# Schematic1.net
KiCad netlist of a schematic drawn in Altium Designer
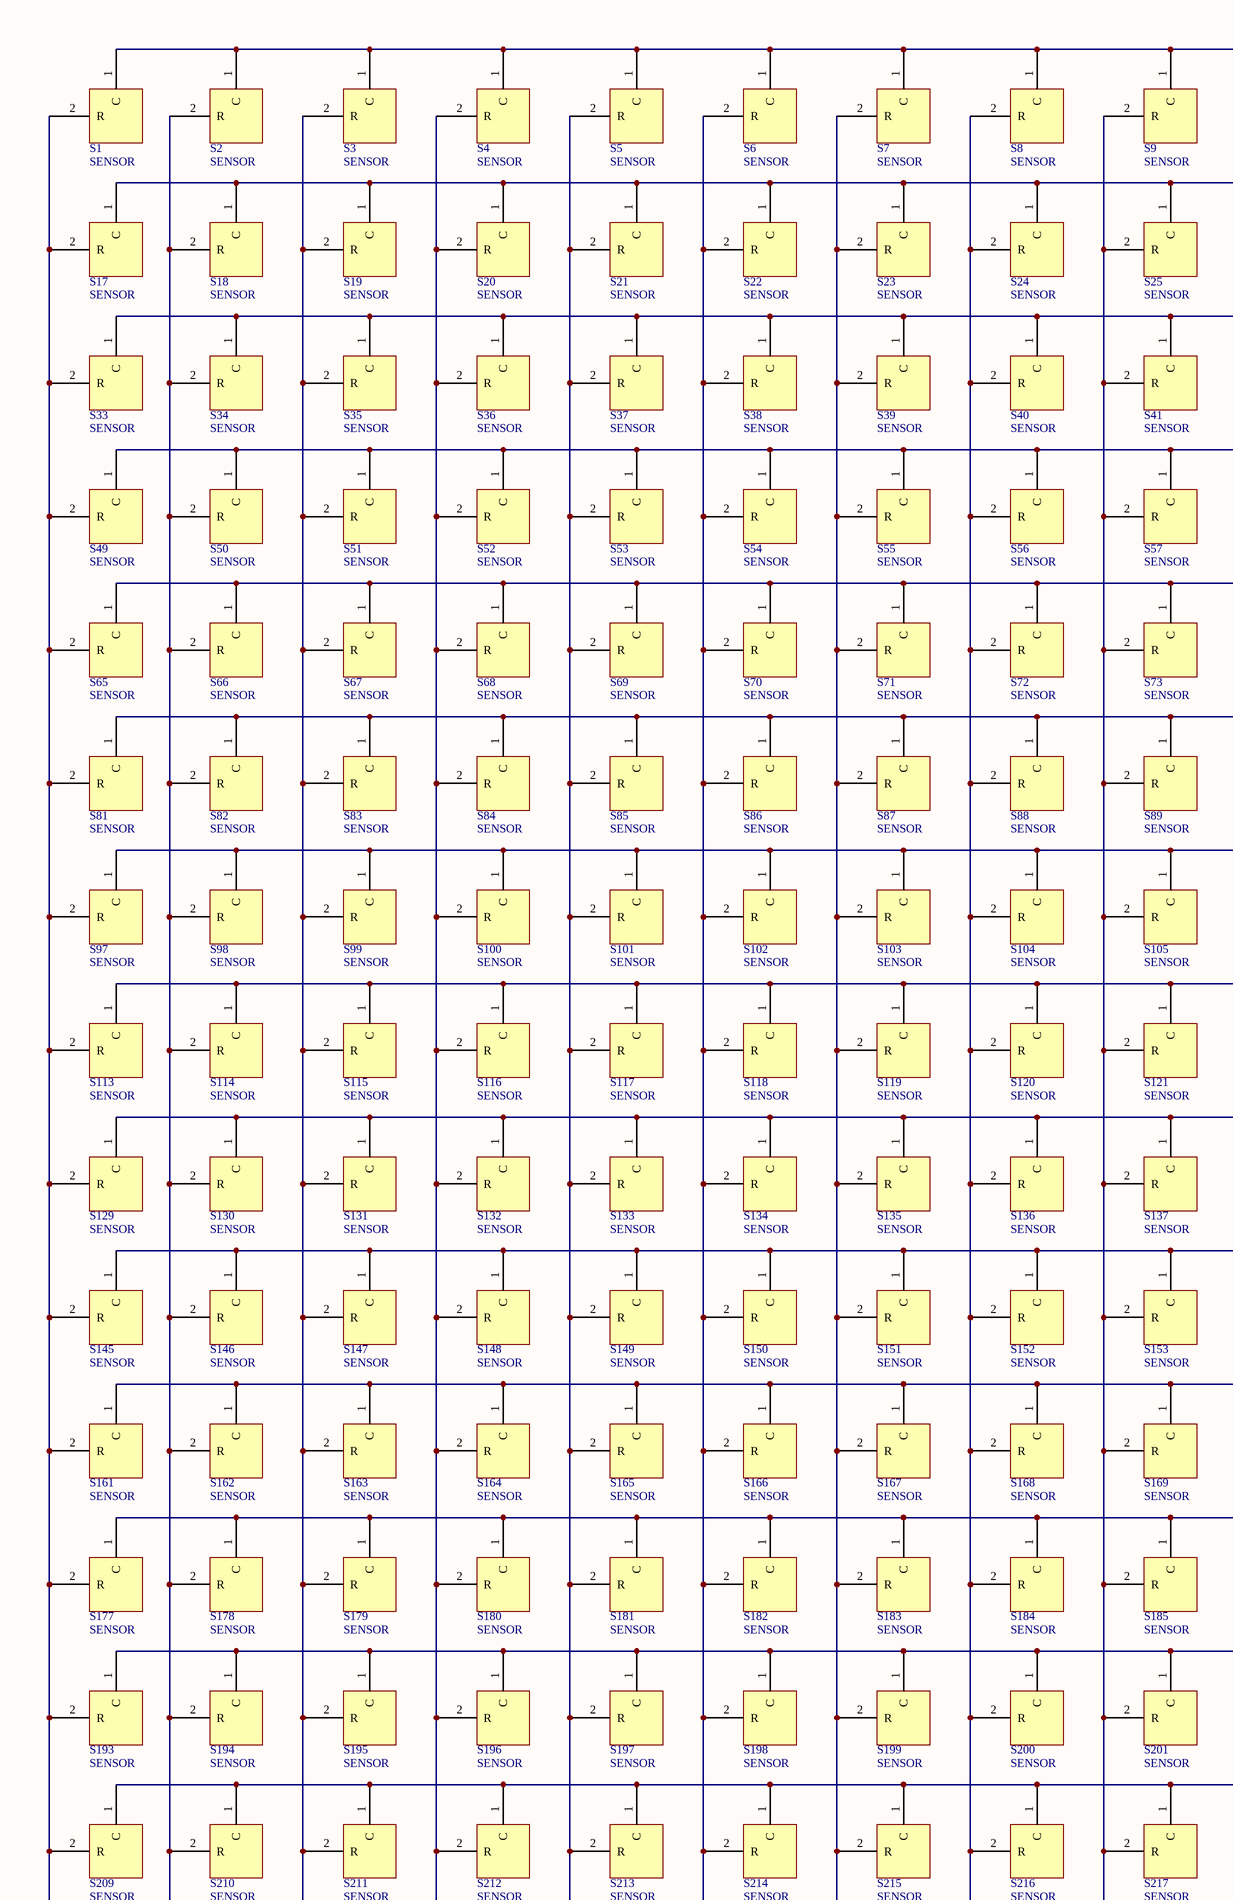
[diagram p0: Schematic1.SchDoc, top left]
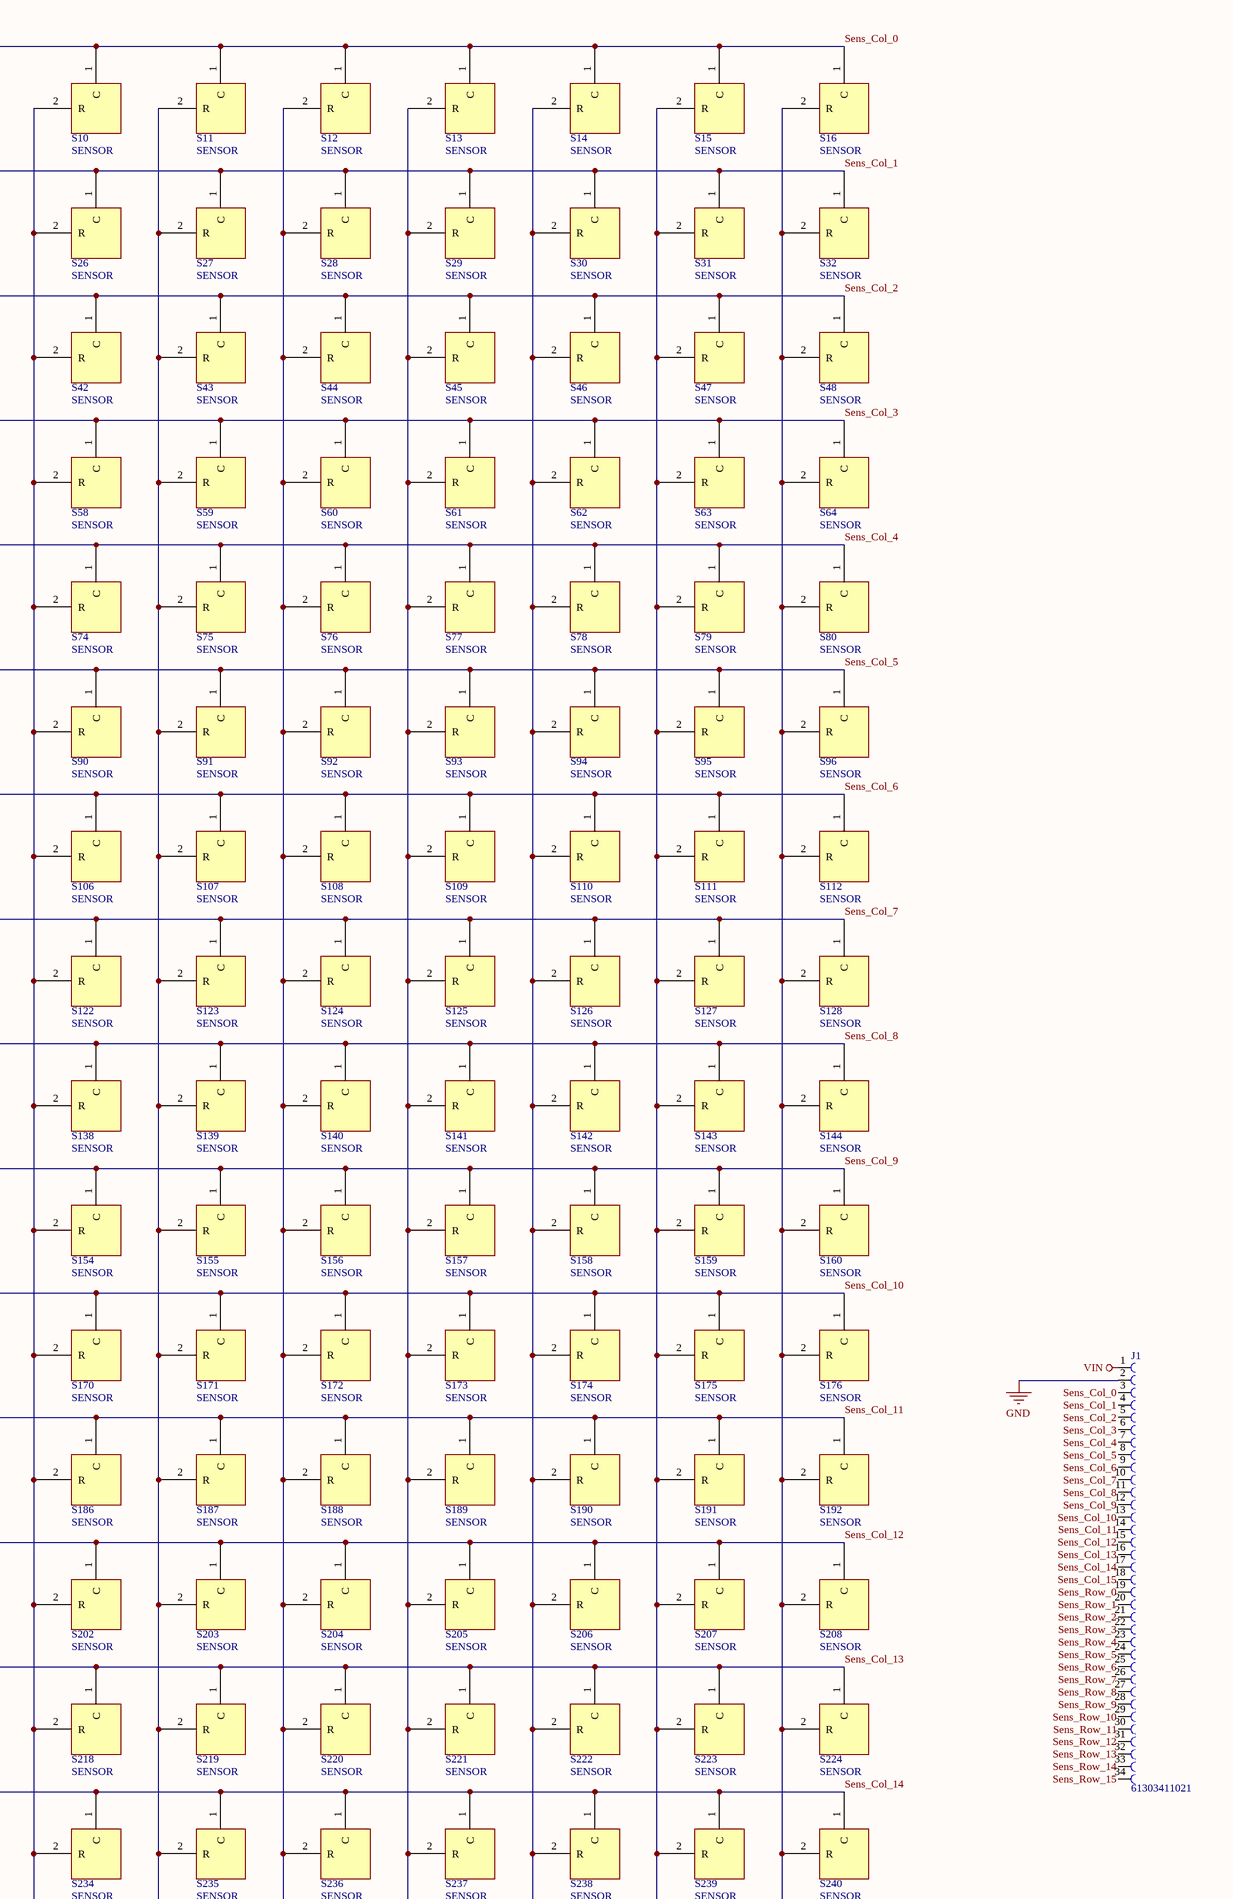
[diagram p1: Schematic1.SchDoc, top right]
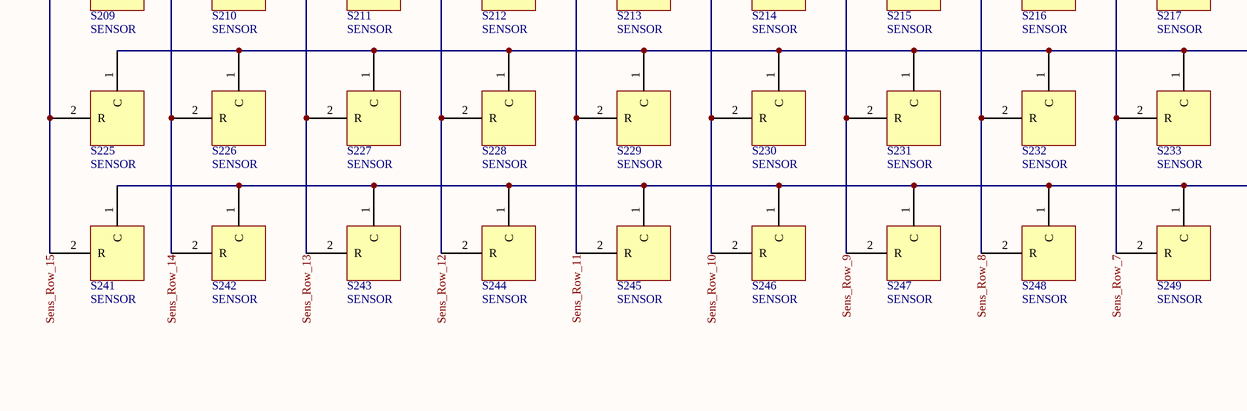
[diagram p2: Schematic1.SchDoc, bottom left]
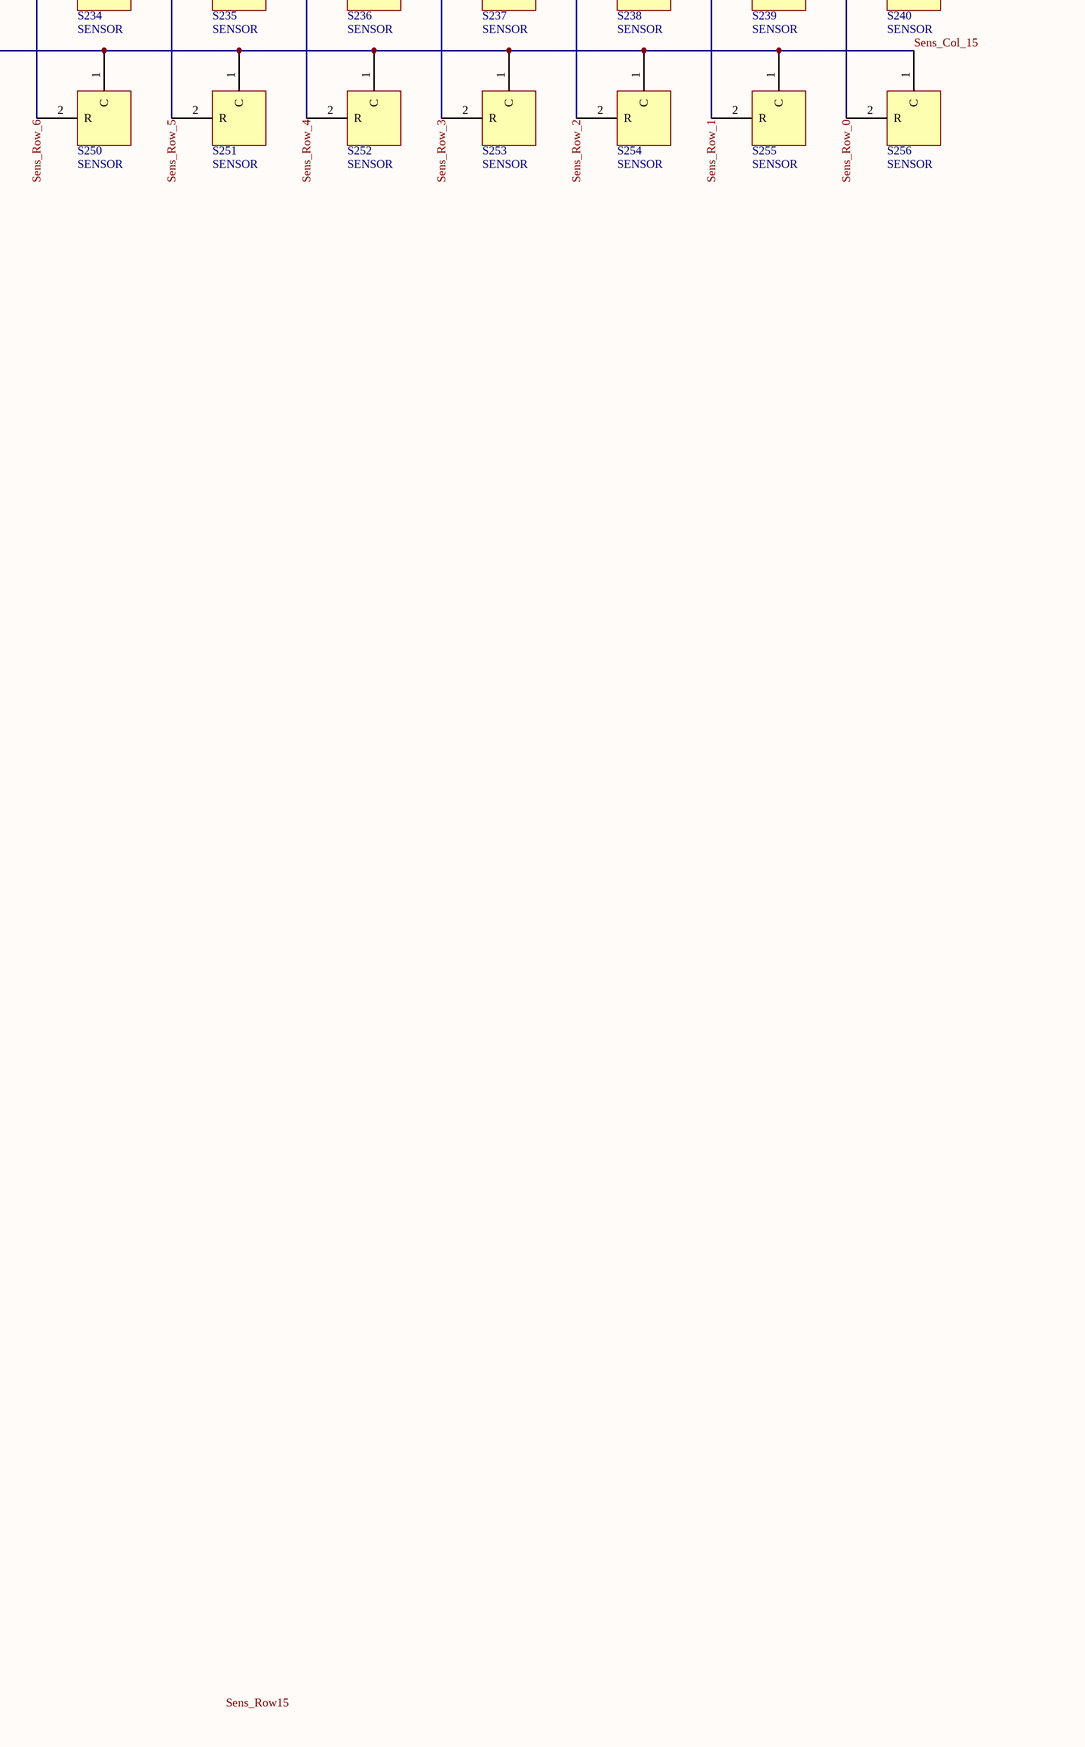
[diagram p3: Schematic1.SchDoc, bottom right]

(export (version "E")
  (design (tool "Eeschema 10.0.6"))
  (components
    (comp (ref "J1")
      (value "61303411021")
      (footprint "61303411021")
      (fields (field (name "MF") "{'manufacturer': u'~{W}xfcrth Elektronik'}"))
      (libsource (lib "SnapEDA_Library") (part "61303411021"))
    )
    (comp (ref "S1") (value "SENSOR") (footprint "SENSOR") (libsource (lib "SENSOR") (part "SENSOR")))
    (comp (ref "S2") (value "SENSOR") (footprint "SENSOR") (libsource (lib "SENSOR") (part "SENSOR")))
    (comp (ref "S3") (value "SENSOR") (footprint "SENSOR") (libsource (lib "SENSOR") (part "SENSOR")))
    (comp (ref "S4") (value "SENSOR") (footprint "SENSOR") (libsource (lib "SENSOR") (part "SENSOR")))
    (comp (ref "S5") (value "SENSOR") (footprint "SENSOR") (libsource (lib "SENSOR") (part "SENSOR")))
    (comp (ref "S6") (value "SENSOR") (footprint "SENSOR") (libsource (lib "SENSOR") (part "SENSOR")))
    (comp (ref "S7") (value "SENSOR") (footprint "SENSOR") (libsource (lib "SENSOR") (part "SENSOR")))
    (comp (ref "S8") (value "SENSOR") (footprint "SENSOR") (libsource (lib "SENSOR") (part "SENSOR")))
    (comp (ref "S9") (value "SENSOR") (footprint "SENSOR") (libsource (lib "SENSOR") (part "SENSOR")))
    (comp (ref "S10") (value "SENSOR") (footprint "SENSOR") (libsource (lib "SENSOR") (part "SENSOR")))
    (comp (ref "S11") (value "SENSOR") (footprint "SENSOR") (libsource (lib "SENSOR") (part "SENSOR")))
    (comp (ref "S12") (value "SENSOR") (footprint "SENSOR") (libsource (lib "SENSOR") (part "SENSOR")))
    (comp (ref "S13") (value "SENSOR") (footprint "SENSOR") (libsource (lib "SENSOR") (part "SENSOR")))
    (comp (ref "S14") (value "SENSOR") (footprint "SENSOR") (libsource (lib "SENSOR") (part "SENSOR")))
    (comp (ref "S15") (value "SENSOR") (footprint "SENSOR") (libsource (lib "SENSOR") (part "SENSOR")))
    (comp (ref "S16") (value "SENSOR") (footprint "SENSOR") (libsource (lib "SENSOR") (part "SENSOR")))
    (comp (ref "S17") (value "SENSOR") (footprint "SENSOR") (libsource (lib "SENSOR") (part "SENSOR")))
    (comp (ref "S18") (value "SENSOR") (footprint "SENSOR") (libsource (lib "SENSOR") (part "SENSOR")))
    (comp (ref "S19") (value "SENSOR") (footprint "SENSOR") (libsource (lib "SENSOR") (part "SENSOR")))
    (comp (ref "S20") (value "SENSOR") (footprint "SENSOR") (libsource (lib "SENSOR") (part "SENSOR")))
    (comp (ref "S21") (value "SENSOR") (footprint "SENSOR") (libsource (lib "SENSOR") (part "SENSOR")))
    (comp (ref "S22") (value "SENSOR") (footprint "SENSOR") (libsource (lib "SENSOR") (part "SENSOR")))
    (comp (ref "S23") (value "SENSOR") (footprint "SENSOR") (libsource (lib "SENSOR") (part "SENSOR")))
    (comp (ref "S24") (value "SENSOR") (footprint "SENSOR") (libsource (lib "SENSOR") (part "SENSOR")))
    (comp (ref "S25") (value "SENSOR") (footprint "SENSOR") (libsource (lib "SENSOR") (part "SENSOR")))
    (comp (ref "S26") (value "SENSOR") (footprint "SENSOR") (libsource (lib "SENSOR") (part "SENSOR")))
    (comp (ref "S27") (value "SENSOR") (footprint "SENSOR") (libsource (lib "SENSOR") (part "SENSOR")))
    (comp (ref "S28") (value "SENSOR") (footprint "SENSOR") (libsource (lib "SENSOR") (part "SENSOR")))
    (comp (ref "S29") (value "SENSOR") (footprint "SENSOR") (libsource (lib "SENSOR") (part "SENSOR")))
    (comp (ref "S30") (value "SENSOR") (footprint "SENSOR") (libsource (lib "SENSOR") (part "SENSOR")))
    (comp (ref "S31") (value "SENSOR") (footprint "SENSOR") (libsource (lib "SENSOR") (part "SENSOR")))
    (comp (ref "S32") (value "SENSOR") (footprint "SENSOR") (libsource (lib "SENSOR") (part "SENSOR")))
    (comp (ref "S33") (value "SENSOR") (footprint "SENSOR") (libsource (lib "SENSOR") (part "SENSOR")))
    (comp (ref "S34") (value "SENSOR") (footprint "SENSOR") (libsource (lib "SENSOR") (part "SENSOR")))
    (comp (ref "S35") (value "SENSOR") (footprint "SENSOR") (libsource (lib "SENSOR") (part "SENSOR")))
    (comp (ref "S36") (value "SENSOR") (footprint "SENSOR") (libsource (lib "SENSOR") (part "SENSOR")))
    (comp (ref "S37") (value "SENSOR") (footprint "SENSOR") (libsource (lib "SENSOR") (part "SENSOR")))
    (comp (ref "S38") (value "SENSOR") (footprint "SENSOR") (libsource (lib "SENSOR") (part "SENSOR")))
    (comp (ref "S39") (value "SENSOR") (footprint "SENSOR") (libsource (lib "SENSOR") (part "SENSOR")))
    (comp (ref "S40") (value "SENSOR") (footprint "SENSOR") (libsource (lib "SENSOR") (part "SENSOR")))
    (comp (ref "S41") (value "SENSOR") (footprint "SENSOR") (libsource (lib "SENSOR") (part "SENSOR")))
    (comp (ref "S42") (value "SENSOR") (footprint "SENSOR") (libsource (lib "SENSOR") (part "SENSOR")))
    (comp (ref "S43") (value "SENSOR") (footprint "SENSOR") (libsource (lib "SENSOR") (part "SENSOR")))
    (comp (ref "S44") (value "SENSOR") (footprint "SENSOR") (libsource (lib "SENSOR") (part "SENSOR")))
    (comp (ref "S45") (value "SENSOR") (footprint "SENSOR") (libsource (lib "SENSOR") (part "SENSOR")))
    (comp (ref "S46") (value "SENSOR") (footprint "SENSOR") (libsource (lib "SENSOR") (part "SENSOR")))
    (comp (ref "S47") (value "SENSOR") (footprint "SENSOR") (libsource (lib "SENSOR") (part "SENSOR")))
    (comp (ref "S48") (value "SENSOR") (footprint "SENSOR") (libsource (lib "SENSOR") (part "SENSOR")))
    (comp (ref "S49") (value "SENSOR") (footprint "SENSOR") (libsource (lib "SENSOR") (part "SENSOR")))
    (comp (ref "S50") (value "SENSOR") (footprint "SENSOR") (libsource (lib "SENSOR") (part "SENSOR")))
    (comp (ref "S51") (value "SENSOR") (footprint "SENSOR") (libsource (lib "SENSOR") (part "SENSOR")))
    (comp (ref "S52") (value "SENSOR") (footprint "SENSOR") (libsource (lib "SENSOR") (part "SENSOR")))
    (comp (ref "S53") (value "SENSOR") (footprint "SENSOR") (libsource (lib "SENSOR") (part "SENSOR")))
    (comp (ref "S54") (value "SENSOR") (footprint "SENSOR") (libsource (lib "SENSOR") (part "SENSOR")))
    (comp (ref "S55") (value "SENSOR") (footprint "SENSOR") (libsource (lib "SENSOR") (part "SENSOR")))
    (comp (ref "S56") (value "SENSOR") (footprint "SENSOR") (libsource (lib "SENSOR") (part "SENSOR")))
    (comp (ref "S57") (value "SENSOR") (footprint "SENSOR") (libsource (lib "SENSOR") (part "SENSOR")))
    (comp (ref "S58") (value "SENSOR") (footprint "SENSOR") (libsource (lib "SENSOR") (part "SENSOR")))
    (comp (ref "S59") (value "SENSOR") (footprint "SENSOR") (libsource (lib "SENSOR") (part "SENSOR")))
    (comp (ref "S60") (value "SENSOR") (footprint "SENSOR") (libsource (lib "SENSOR") (part "SENSOR")))
    (comp (ref "S61") (value "SENSOR") (footprint "SENSOR") (libsource (lib "SENSOR") (part "SENSOR")))
    (comp (ref "S62") (value "SENSOR") (footprint "SENSOR") (libsource (lib "SENSOR") (part "SENSOR")))
    (comp (ref "S63") (value "SENSOR") (footprint "SENSOR") (libsource (lib "SENSOR") (part "SENSOR")))
    (comp (ref "S64") (value "SENSOR") (footprint "SENSOR") (libsource (lib "SENSOR") (part "SENSOR")))
    (comp (ref "S65") (value "SENSOR") (footprint "SENSOR") (libsource (lib "SENSOR") (part "SENSOR")))
    (comp (ref "S66") (value "SENSOR") (footprint "SENSOR") (libsource (lib "SENSOR") (part "SENSOR")))
    (comp (ref "S67") (value "SENSOR") (footprint "SENSOR") (libsource (lib "SENSOR") (part "SENSOR")))
    (comp (ref "S68") (value "SENSOR") (footprint "SENSOR") (libsource (lib "SENSOR") (part "SENSOR")))
    (comp (ref "S69") (value "SENSOR") (footprint "SENSOR") (libsource (lib "SENSOR") (part "SENSOR")))
    (comp (ref "S70") (value "SENSOR") (footprint "SENSOR") (libsource (lib "SENSOR") (part "SENSOR")))
    (comp (ref "S71") (value "SENSOR") (footprint "SENSOR") (libsource (lib "SENSOR") (part "SENSOR")))
    (comp (ref "S72") (value "SENSOR") (footprint "SENSOR") (libsource (lib "SENSOR") (part "SENSOR")))
    (comp (ref "S73") (value "SENSOR") (footprint "SENSOR") (libsource (lib "SENSOR") (part "SENSOR")))
    (comp (ref "S74") (value "SENSOR") (footprint "SENSOR") (libsource (lib "SENSOR") (part "SENSOR")))
    (comp (ref "S75") (value "SENSOR") (footprint "SENSOR") (libsource (lib "SENSOR") (part "SENSOR")))
    (comp (ref "S76") (value "SENSOR") (footprint "SENSOR") (libsource (lib "SENSOR") (part "SENSOR")))
    (comp (ref "S77") (value "SENSOR") (footprint "SENSOR") (libsource (lib "SENSOR") (part "SENSOR")))
    (comp (ref "S78") (value "SENSOR") (footprint "SENSOR") (libsource (lib "SENSOR") (part "SENSOR")))
    (comp (ref "S79") (value "SENSOR") (footprint "SENSOR") (libsource (lib "SENSOR") (part "SENSOR")))
    (comp (ref "S80") (value "SENSOR") (footprint "SENSOR") (libsource (lib "SENSOR") (part "SENSOR")))
    (comp (ref "S81") (value "SENSOR") (footprint "SENSOR") (libsource (lib "SENSOR") (part "SENSOR")))
    (comp (ref "S82") (value "SENSOR") (footprint "SENSOR") (libsource (lib "SENSOR") (part "SENSOR")))
    (comp (ref "S83") (value "SENSOR") (footprint "SENSOR") (libsource (lib "SENSOR") (part "SENSOR")))
    (comp (ref "S84") (value "SENSOR") (footprint "SENSOR") (libsource (lib "SENSOR") (part "SENSOR")))
    (comp (ref "S85") (value "SENSOR") (footprint "SENSOR") (libsource (lib "SENSOR") (part "SENSOR")))
    (comp (ref "S86") (value "SENSOR") (footprint "SENSOR") (libsource (lib "SENSOR") (part "SENSOR")))
    (comp (ref "S87") (value "SENSOR") (footprint "SENSOR") (libsource (lib "SENSOR") (part "SENSOR")))
    (comp (ref "S88") (value "SENSOR") (footprint "SENSOR") (libsource (lib "SENSOR") (part "SENSOR")))
    (comp (ref "S89") (value "SENSOR") (footprint "SENSOR") (libsource (lib "SENSOR") (part "SENSOR")))
    (comp (ref "S90") (value "SENSOR") (footprint "SENSOR") (libsource (lib "SENSOR") (part "SENSOR")))
    (comp (ref "S91") (value "SENSOR") (footprint "SENSOR") (libsource (lib "SENSOR") (part "SENSOR")))
    (comp (ref "S92") (value "SENSOR") (footprint "SENSOR") (libsource (lib "SENSOR") (part "SENSOR")))
    (comp (ref "S93") (value "SENSOR") (footprint "SENSOR") (libsource (lib "SENSOR") (part "SENSOR")))
    (comp (ref "S94") (value "SENSOR") (footprint "SENSOR") (libsource (lib "SENSOR") (part "SENSOR")))
    (comp (ref "S95") (value "SENSOR") (footprint "SENSOR") (libsource (lib "SENSOR") (part "SENSOR")))
    (comp (ref "S96") (value "SENSOR") (footprint "SENSOR") (libsource (lib "SENSOR") (part "SENSOR")))
    (comp (ref "S97") (value "SENSOR") (footprint "SENSOR") (libsource (lib "SENSOR") (part "SENSOR")))
    (comp (ref "S98") (value "SENSOR") (footprint "SENSOR") (libsource (lib "SENSOR") (part "SENSOR")))
    (comp (ref "S99") (value "SENSOR") (footprint "SENSOR") (libsource (lib "SENSOR") (part "SENSOR")))
    (comp (ref "S100") (value "SENSOR") (footprint "SENSOR") (libsource (lib "SENSOR") (part "SENSOR")))
    (comp (ref "S101") (value "SENSOR") (footprint "SENSOR") (libsource (lib "SENSOR") (part "SENSOR")))
    (comp (ref "S102") (value "SENSOR") (footprint "SENSOR") (libsource (lib "SENSOR") (part "SENSOR")))
    (comp (ref "S103") (value "SENSOR") (footprint "SENSOR") (libsource (lib "SENSOR") (part "SENSOR")))
    (comp (ref "S104") (value "SENSOR") (footprint "SENSOR") (libsource (lib "SENSOR") (part "SENSOR")))
    (comp (ref "S105") (value "SENSOR") (footprint "SENSOR") (libsource (lib "SENSOR") (part "SENSOR")))
    (comp (ref "S106") (value "SENSOR") (footprint "SENSOR") (libsource (lib "SENSOR") (part "SENSOR")))
    (comp (ref "S107") (value "SENSOR") (footprint "SENSOR") (libsource (lib "SENSOR") (part "SENSOR")))
    (comp (ref "S108") (value "SENSOR") (footprint "SENSOR") (libsource (lib "SENSOR") (part "SENSOR")))
    (comp (ref "S109") (value "SENSOR") (footprint "SENSOR") (libsource (lib "SENSOR") (part "SENSOR")))
    (comp (ref "S110") (value "SENSOR") (footprint "SENSOR") (libsource (lib "SENSOR") (part "SENSOR")))
    (comp (ref "S111") (value "SENSOR") (footprint "SENSOR") (libsource (lib "SENSOR") (part "SENSOR")))
    (comp (ref "S112") (value "SENSOR") (footprint "SENSOR") (libsource (lib "SENSOR") (part "SENSOR")))
    (comp (ref "S113") (value "SENSOR") (footprint "SENSOR") (libsource (lib "SENSOR") (part "SENSOR")))
    (comp (ref "S114") (value "SENSOR") (footprint "SENSOR") (libsource (lib "SENSOR") (part "SENSOR")))
    (comp (ref "S115") (value "SENSOR") (footprint "SENSOR") (libsource (lib "SENSOR") (part "SENSOR")))
    (comp (ref "S116") (value "SENSOR") (footprint "SENSOR") (libsource (lib "SENSOR") (part "SENSOR")))
    (comp (ref "S117") (value "SENSOR") (footprint "SENSOR") (libsource (lib "SENSOR") (part "SENSOR")))
    (comp (ref "S118") (value "SENSOR") (footprint "SENSOR") (libsource (lib "SENSOR") (part "SENSOR")))
    (comp (ref "S119") (value "SENSOR") (footprint "SENSOR") (libsource (lib "SENSOR") (part "SENSOR")))
    (comp (ref "S120") (value "SENSOR") (footprint "SENSOR") (libsource (lib "SENSOR") (part "SENSOR")))
    (comp (ref "S121") (value "SENSOR") (footprint "SENSOR") (libsource (lib "SENSOR") (part "SENSOR")))
    (comp (ref "S122") (value "SENSOR") (footprint "SENSOR") (libsource (lib "SENSOR") (part "SENSOR")))
    (comp (ref "S123") (value "SENSOR") (footprint "SENSOR") (libsource (lib "SENSOR") (part "SENSOR")))
    (comp (ref "S124") (value "SENSOR") (footprint "SENSOR") (libsource (lib "SENSOR") (part "SENSOR")))
    (comp (ref "S125") (value "SENSOR") (footprint "SENSOR") (libsource (lib "SENSOR") (part "SENSOR")))
    (comp (ref "S126") (value "SENSOR") (footprint "SENSOR") (libsource (lib "SENSOR") (part "SENSOR")))
    (comp (ref "S127") (value "SENSOR") (footprint "SENSOR") (libsource (lib "SENSOR") (part "SENSOR")))
    (comp (ref "S128") (value "SENSOR") (footprint "SENSOR") (libsource (lib "SENSOR") (part "SENSOR")))
    (comp (ref "S129") (value "SENSOR") (footprint "SENSOR") (libsource (lib "SENSOR") (part "SENSOR")))
    (comp (ref "S130") (value "SENSOR") (footprint "SENSOR") (libsource (lib "SENSOR") (part "SENSOR")))
    (comp (ref "S131") (value "SENSOR") (footprint "SENSOR") (libsource (lib "SENSOR") (part "SENSOR")))
    (comp (ref "S132") (value "SENSOR") (footprint "SENSOR") (libsource (lib "SENSOR") (part "SENSOR")))
    (comp (ref "S133") (value "SENSOR") (footprint "SENSOR") (libsource (lib "SENSOR") (part "SENSOR")))
    (comp (ref "S134") (value "SENSOR") (footprint "SENSOR") (libsource (lib "SENSOR") (part "SENSOR")))
    (comp (ref "S135") (value "SENSOR") (footprint "SENSOR") (libsource (lib "SENSOR") (part "SENSOR")))
    (comp (ref "S136") (value "SENSOR") (footprint "SENSOR") (libsource (lib "SENSOR") (part "SENSOR")))
    (comp (ref "S137") (value "SENSOR") (footprint "SENSOR") (libsource (lib "SENSOR") (part "SENSOR")))
    (comp (ref "S138") (value "SENSOR") (footprint "SENSOR") (libsource (lib "SENSOR") (part "SENSOR")))
    (comp (ref "S139") (value "SENSOR") (footprint "SENSOR") (libsource (lib "SENSOR") (part "SENSOR")))
    (comp (ref "S140") (value "SENSOR") (footprint "SENSOR") (libsource (lib "SENSOR") (part "SENSOR")))
    (comp (ref "S141") (value "SENSOR") (footprint "SENSOR") (libsource (lib "SENSOR") (part "SENSOR")))
    (comp (ref "S142") (value "SENSOR") (footprint "SENSOR") (libsource (lib "SENSOR") (part "SENSOR")))
    (comp (ref "S143") (value "SENSOR") (footprint "SENSOR") (libsource (lib "SENSOR") (part "SENSOR")))
    (comp (ref "S144") (value "SENSOR") (footprint "SENSOR") (libsource (lib "SENSOR") (part "SENSOR")))
    (comp (ref "S145") (value "SENSOR") (footprint "SENSOR") (libsource (lib "SENSOR") (part "SENSOR")))
    (comp (ref "S146") (value "SENSOR") (footprint "SENSOR") (libsource (lib "SENSOR") (part "SENSOR")))
    (comp (ref "S147") (value "SENSOR") (footprint "SENSOR") (libsource (lib "SENSOR") (part "SENSOR")))
    (comp (ref "S148") (value "SENSOR") (footprint "SENSOR") (libsource (lib "SENSOR") (part "SENSOR")))
    (comp (ref "S149") (value "SENSOR") (footprint "SENSOR") (libsource (lib "SENSOR") (part "SENSOR")))
    (comp (ref "S150") (value "SENSOR") (footprint "SENSOR") (libsource (lib "SENSOR") (part "SENSOR")))
    (comp (ref "S151") (value "SENSOR") (footprint "SENSOR") (libsource (lib "SENSOR") (part "SENSOR")))
    (comp (ref "S152") (value "SENSOR") (footprint "SENSOR") (libsource (lib "SENSOR") (part "SENSOR")))
    (comp (ref "S153") (value "SENSOR") (footprint "SENSOR") (libsource (lib "SENSOR") (part "SENSOR")))
    (comp (ref "S154") (value "SENSOR") (footprint "SENSOR") (libsource (lib "SENSOR") (part "SENSOR")))
    (comp (ref "S155") (value "SENSOR") (footprint "SENSOR") (libsource (lib "SENSOR") (part "SENSOR")))
    (comp (ref "S156") (value "SENSOR") (footprint "SENSOR") (libsource (lib "SENSOR") (part "SENSOR")))
    (comp (ref "S157") (value "SENSOR") (footprint "SENSOR") (libsource (lib "SENSOR") (part "SENSOR")))
    (comp (ref "S158") (value "SENSOR") (footprint "SENSOR") (libsource (lib "SENSOR") (part "SENSOR")))
    (comp (ref "S159") (value "SENSOR") (footprint "SENSOR") (libsource (lib "SENSOR") (part "SENSOR")))
    (comp (ref "S160") (value "SENSOR") (footprint "SENSOR") (libsource (lib "SENSOR") (part "SENSOR")))
    (comp (ref "S161") (value "SENSOR") (footprint "SENSOR") (libsource (lib "SENSOR") (part "SENSOR")))
    (comp (ref "S162") (value "SENSOR") (footprint "SENSOR") (libsource (lib "SENSOR") (part "SENSOR")))
    (comp (ref "S163") (value "SENSOR") (footprint "SENSOR") (libsource (lib "SENSOR") (part "SENSOR")))
    (comp (ref "S164") (value "SENSOR") (footprint "SENSOR") (libsource (lib "SENSOR") (part "SENSOR")))
    (comp (ref "S165") (value "SENSOR") (footprint "SENSOR") (libsource (lib "SENSOR") (part "SENSOR")))
    (comp (ref "S166") (value "SENSOR") (footprint "SENSOR") (libsource (lib "SENSOR") (part "SENSOR")))
    (comp (ref "S167") (value "SENSOR") (footprint "SENSOR") (libsource (lib "SENSOR") (part "SENSOR")))
    (comp (ref "S168") (value "SENSOR") (footprint "SENSOR") (libsource (lib "SENSOR") (part "SENSOR")))
    (comp (ref "S169") (value "SENSOR") (footprint "SENSOR") (libsource (lib "SENSOR") (part "SENSOR")))
    (comp (ref "S170") (value "SENSOR") (footprint "SENSOR") (libsource (lib "SENSOR") (part "SENSOR")))
    (comp (ref "S171") (value "SENSOR") (footprint "SENSOR") (libsource (lib "SENSOR") (part "SENSOR")))
    (comp (ref "S172") (value "SENSOR") (footprint "SENSOR") (libsource (lib "SENSOR") (part "SENSOR")))
    (comp (ref "S173") (value "SENSOR") (footprint "SENSOR") (libsource (lib "SENSOR") (part "SENSOR")))
    (comp (ref "S174") (value "SENSOR") (footprint "SENSOR") (libsource (lib "SENSOR") (part "SENSOR")))
    (comp (ref "S175") (value "SENSOR") (footprint "SENSOR") (libsource (lib "SENSOR") (part "SENSOR")))
    (comp (ref "S176") (value "SENSOR") (footprint "SENSOR") (libsource (lib "SENSOR") (part "SENSOR")))
    (comp (ref "S177") (value "SENSOR") (footprint "SENSOR") (libsource (lib "SENSOR") (part "SENSOR")))
    (comp (ref "S178") (value "SENSOR") (footprint "SENSOR") (libsource (lib "SENSOR") (part "SENSOR")))
    (comp (ref "S179") (value "SENSOR") (footprint "SENSOR") (libsource (lib "SENSOR") (part "SENSOR")))
    (comp (ref "S180") (value "SENSOR") (footprint "SENSOR") (libsource (lib "SENSOR") (part "SENSOR")))
    (comp (ref "S181") (value "SENSOR") (footprint "SENSOR") (libsource (lib "SENSOR") (part "SENSOR")))
    (comp (ref "S182") (value "SENSOR") (footprint "SENSOR") (libsource (lib "SENSOR") (part "SENSOR")))
    (comp (ref "S183") (value "SENSOR") (footprint "SENSOR") (libsource (lib "SENSOR") (part "SENSOR")))
    (comp (ref "S184") (value "SENSOR") (footprint "SENSOR") (libsource (lib "SENSOR") (part "SENSOR")))
    (comp (ref "S185") (value "SENSOR") (footprint "SENSOR") (libsource (lib "SENSOR") (part "SENSOR")))
    (comp (ref "S186") (value "SENSOR") (footprint "SENSOR") (libsource (lib "SENSOR") (part "SENSOR")))
    (comp (ref "S187") (value "SENSOR") (footprint "SENSOR") (libsource (lib "SENSOR") (part "SENSOR")))
    (comp (ref "S188") (value "SENSOR") (footprint "SENSOR") (libsource (lib "SENSOR") (part "SENSOR")))
    (comp (ref "S189") (value "SENSOR") (footprint "SENSOR") (libsource (lib "SENSOR") (part "SENSOR")))
    (comp (ref "S190") (value "SENSOR") (footprint "SENSOR") (libsource (lib "SENSOR") (part "SENSOR")))
    (comp (ref "S191") (value "SENSOR") (footprint "SENSOR") (libsource (lib "SENSOR") (part "SENSOR")))
    (comp (ref "S192") (value "SENSOR") (footprint "SENSOR") (libsource (lib "SENSOR") (part "SENSOR")))
    (comp (ref "S193") (value "SENSOR") (footprint "SENSOR") (libsource (lib "SENSOR") (part "SENSOR")))
    (comp (ref "S194") (value "SENSOR") (footprint "SENSOR") (libsource (lib "SENSOR") (part "SENSOR")))
    (comp (ref "S195") (value "SENSOR") (footprint "SENSOR") (libsource (lib "SENSOR") (part "SENSOR")))
    (comp (ref "S196") (value "SENSOR") (footprint "SENSOR") (libsource (lib "SENSOR") (part "SENSOR")))
    (comp (ref "S197") (value "SENSOR") (footprint "SENSOR") (libsource (lib "SENSOR") (part "SENSOR")))
    (comp (ref "S198") (value "SENSOR") (footprint "SENSOR") (libsource (lib "SENSOR") (part "SENSOR")))
    (comp (ref "S199") (value "SENSOR") (footprint "SENSOR") (libsource (lib "SENSOR") (part "SENSOR")))
    (comp (ref "S200") (value "SENSOR") (footprint "SENSOR") (libsource (lib "SENSOR") (part "SENSOR")))
    (comp (ref "S201") (value "SENSOR") (footprint "SENSOR") (libsource (lib "SENSOR") (part "SENSOR")))
    (comp (ref "S202") (value "SENSOR") (footprint "SENSOR") (libsource (lib "SENSOR") (part "SENSOR")))
    (comp (ref "S203") (value "SENSOR") (footprint "SENSOR") (libsource (lib "SENSOR") (part "SENSOR")))
    (comp (ref "S204") (value "SENSOR") (footprint "SENSOR") (libsource (lib "SENSOR") (part "SENSOR")))
    (comp (ref "S205") (value "SENSOR") (footprint "SENSOR") (libsource (lib "SENSOR") (part "SENSOR")))
    (comp (ref "S206") (value "SENSOR") (footprint "SENSOR") (libsource (lib "SENSOR") (part "SENSOR")))
    (comp (ref "S207") (value "SENSOR") (footprint "SENSOR") (libsource (lib "SENSOR") (part "SENSOR")))
    (comp (ref "S208") (value "SENSOR") (footprint "SENSOR") (libsource (lib "SENSOR") (part "SENSOR")))
    (comp (ref "S209") (value "SENSOR") (footprint "SENSOR") (libsource (lib "SENSOR") (part "SENSOR")))
    (comp (ref "S210") (value "SENSOR") (footprint "SENSOR") (libsource (lib "SENSOR") (part "SENSOR")))
    (comp (ref "S211") (value "SENSOR") (footprint "SENSOR") (libsource (lib "SENSOR") (part "SENSOR")))
    (comp (ref "S212") (value "SENSOR") (footprint "SENSOR") (libsource (lib "SENSOR") (part "SENSOR")))
    (comp (ref "S213") (value "SENSOR") (footprint "SENSOR") (libsource (lib "SENSOR") (part "SENSOR")))
    (comp (ref "S214") (value "SENSOR") (footprint "SENSOR") (libsource (lib "SENSOR") (part "SENSOR")))
    (comp (ref "S215") (value "SENSOR") (footprint "SENSOR") (libsource (lib "SENSOR") (part "SENSOR")))
    (comp (ref "S216") (value "SENSOR") (footprint "SENSOR") (libsource (lib "SENSOR") (part "SENSOR")))
    (comp (ref "S217") (value "SENSOR") (footprint "SENSOR") (libsource (lib "SENSOR") (part "SENSOR")))
    (comp (ref "S218") (value "SENSOR") (footprint "SENSOR") (libsource (lib "SENSOR") (part "SENSOR")))
    (comp (ref "S219") (value "SENSOR") (footprint "SENSOR") (libsource (lib "SENSOR") (part "SENSOR")))
    (comp (ref "S220") (value "SENSOR") (footprint "SENSOR") (libsource (lib "SENSOR") (part "SENSOR")))
    (comp (ref "S221") (value "SENSOR") (footprint "SENSOR") (libsource (lib "SENSOR") (part "SENSOR")))
    (comp (ref "S222") (value "SENSOR") (footprint "SENSOR") (libsource (lib "SENSOR") (part "SENSOR")))
    (comp (ref "S223") (value "SENSOR") (footprint "SENSOR") (libsource (lib "SENSOR") (part "SENSOR")))
    (comp (ref "S224") (value "SENSOR") (footprint "SENSOR") (libsource (lib "SENSOR") (part "SENSOR")))
    (comp (ref "S225") (value "SENSOR") (footprint "SENSOR") (libsource (lib "SENSOR") (part "SENSOR")))
    (comp (ref "S226") (value "SENSOR") (footprint "SENSOR") (libsource (lib "SENSOR") (part "SENSOR")))
    (comp (ref "S227") (value "SENSOR") (footprint "SENSOR") (libsource (lib "SENSOR") (part "SENSOR")))
    (comp (ref "S228") (value "SENSOR") (footprint "SENSOR") (libsource (lib "SENSOR") (part "SENSOR")))
    (comp (ref "S229") (value "SENSOR") (footprint "SENSOR") (libsource (lib "SENSOR") (part "SENSOR")))
    (comp (ref "S230") (value "SENSOR") (footprint "SENSOR") (libsource (lib "SENSOR") (part "SENSOR")))
    (comp (ref "S231") (value "SENSOR") (footprint "SENSOR") (libsource (lib "SENSOR") (part "SENSOR")))
    (comp (ref "S232") (value "SENSOR") (footprint "SENSOR") (libsource (lib "SENSOR") (part "SENSOR")))
    (comp (ref "S233") (value "SENSOR") (footprint "SENSOR") (libsource (lib "SENSOR") (part "SENSOR")))
    (comp (ref "S234") (value "SENSOR") (footprint "SENSOR") (libsource (lib "SENSOR") (part "SENSOR")))
    (comp (ref "S235") (value "SENSOR") (footprint "SENSOR") (libsource (lib "SENSOR") (part "SENSOR")))
    (comp (ref "S236") (value "SENSOR") (footprint "SENSOR") (libsource (lib "SENSOR") (part "SENSOR")))
    (comp (ref "S237") (value "SENSOR") (footprint "SENSOR") (libsource (lib "SENSOR") (part "SENSOR")))
    (comp (ref "S238") (value "SENSOR") (footprint "SENSOR") (libsource (lib "SENSOR") (part "SENSOR")))
    (comp (ref "S239") (value "SENSOR") (footprint "SENSOR") (libsource (lib "SENSOR") (part "SENSOR")))
    (comp (ref "S240") (value "SENSOR") (footprint "SENSOR") (libsource (lib "SENSOR") (part "SENSOR")))
    (comp (ref "S241") (value "SENSOR") (footprint "SENSOR") (libsource (lib "SENSOR") (part "SENSOR")))
    (comp (ref "S242") (value "SENSOR") (footprint "SENSOR") (libsource (lib "SENSOR") (part "SENSOR")))
    (comp (ref "S243") (value "SENSOR") (footprint "SENSOR") (libsource (lib "SENSOR") (part "SENSOR")))
    (comp (ref "S244") (value "SENSOR") (footprint "SENSOR") (libsource (lib "SENSOR") (part "SENSOR")))
    (comp (ref "S245") (value "SENSOR") (footprint "SENSOR") (libsource (lib "SENSOR") (part "SENSOR")))
    (comp (ref "S246") (value "SENSOR") (footprint "SENSOR") (libsource (lib "SENSOR") (part "SENSOR")))
    (comp (ref "S247") (value "SENSOR") (footprint "SENSOR") (libsource (lib "SENSOR") (part "SENSOR")))
    (comp (ref "S248") (value "SENSOR") (footprint "SENSOR") (libsource (lib "SENSOR") (part "SENSOR")))
    (comp (ref "S249") (value "SENSOR") (footprint "SENSOR") (libsource (lib "SENSOR") (part "SENSOR")))
    (comp (ref "S250") (value "SENSOR") (footprint "SENSOR") (libsource (lib "SENSOR") (part "SENSOR")))
    (comp (ref "S251") (value "SENSOR") (footprint "SENSOR") (libsource (lib "SENSOR") (part "SENSOR")))
    (comp (ref "S252") (value "SENSOR") (footprint "SENSOR") (libsource (lib "SENSOR") (part "SENSOR")))
    (comp (ref "S253") (value "SENSOR") (footprint "SENSOR") (libsource (lib "SENSOR") (part "SENSOR")))
    (comp (ref "S254") (value "SENSOR") (footprint "SENSOR") (libsource (lib "SENSOR") (part "SENSOR")))
    (comp (ref "S255") (value "SENSOR") (footprint "SENSOR") (libsource (lib "SENSOR") (part "SENSOR")))
    (comp (ref "S256") (value "SENSOR") (footprint "SENSOR") (libsource (lib "SENSOR") (part "SENSOR")))
  )
  (nets
    (net (code "1") (name "/Sens_Col_0") (class "Default")
      (node (ref "J1") (pin "3") (pinfunction "3_3") (pintype "passive"))
      (node (ref "S1") (pin "1") (pinfunction "C_1") (pintype "passive"))
      (node (ref "S10") (pin "1") (pinfunction "C_1") (pintype "passive"))
      (node (ref "S11") (pin "1") (pinfunction "C_1") (pintype "passive"))
      (node (ref "S12") (pin "1") (pinfunction "C_1") (pintype "passive"))
      (node (ref "S13") (pin "1") (pinfunction "C_1") (pintype "passive"))
      (node (ref "S14") (pin "1") (pinfunction "C_1") (pintype "passive"))
      (node (ref "S15") (pin "1") (pinfunction "C_1") (pintype "passive"))
      (node (ref "S16") (pin "1") (pinfunction "C_1") (pintype "passive"))
      (node (ref "S2") (pin "1") (pinfunction "C_1") (pintype "passive"))
      (node (ref "S3") (pin "1") (pinfunction "C_1") (pintype "passive"))
      (node (ref "S4") (pin "1") (pinfunction "C_1") (pintype "passive"))
      (node (ref "S5") (pin "1") (pinfunction "C_1") (pintype "passive"))
      (node (ref "S6") (pin "1") (pinfunction "C_1") (pintype "passive"))
      (node (ref "S7") (pin "1") (pinfunction "C_1") (pintype "passive"))
      (node (ref "S8") (pin "1") (pinfunction "C_1") (pintype "passive"))
      (node (ref "S9") (pin "1") (pinfunction "C_1") (pintype "passive"))
    )
    (net (code "2") (name "/Sens_Col_1") (class "Default")
      (node (ref "J1") (pin "4") (pinfunction "4_4") (pintype "passive"))
      (node (ref "S17") (pin "1") (pinfunction "C_1") (pintype "passive"))
      (node (ref "S18") (pin "1") (pinfunction "C_1") (pintype "passive"))
      (node (ref "S19") (pin "1") (pinfunction "C_1") (pintype "passive"))
      (node (ref "S20") (pin "1") (pinfunction "C_1") (pintype "passive"))
      (node (ref "S21") (pin "1") (pinfunction "C_1") (pintype "passive"))
      (node (ref "S22") (pin "1") (pinfunction "C_1") (pintype "passive"))
      (node (ref "S23") (pin "1") (pinfunction "C_1") (pintype "passive"))
      (node (ref "S24") (pin "1") (pinfunction "C_1") (pintype "passive"))
      (node (ref "S25") (pin "1") (pinfunction "C_1") (pintype "passive"))
      (node (ref "S26") (pin "1") (pinfunction "C_1") (pintype "passive"))
      (node (ref "S27") (pin "1") (pinfunction "C_1") (pintype "passive"))
      (node (ref "S28") (pin "1") (pinfunction "C_1") (pintype "passive"))
      (node (ref "S29") (pin "1") (pinfunction "C_1") (pintype "passive"))
      (node (ref "S30") (pin "1") (pinfunction "C_1") (pintype "passive"))
      (node (ref "S31") (pin "1") (pinfunction "C_1") (pintype "passive"))
      (node (ref "S32") (pin "1") (pinfunction "C_1") (pintype "passive"))
    )
    (net (code "3") (name "/Sens_Col_2") (class "Default")
      (node (ref "J1") (pin "5") (pinfunction "5_5") (pintype "passive"))
      (node (ref "S33") (pin "1") (pinfunction "C_1") (pintype "passive"))
      (node (ref "S34") (pin "1") (pinfunction "C_1") (pintype "passive"))
      (node (ref "S35") (pin "1") (pinfunction "C_1") (pintype "passive"))
      (node (ref "S36") (pin "1") (pinfunction "C_1") (pintype "passive"))
      (node (ref "S37") (pin "1") (pinfunction "C_1") (pintype "passive"))
      (node (ref "S38") (pin "1") (pinfunction "C_1") (pintype "passive"))
      (node (ref "S39") (pin "1") (pinfunction "C_1") (pintype "passive"))
      (node (ref "S40") (pin "1") (pinfunction "C_1") (pintype "passive"))
      (node (ref "S41") (pin "1") (pinfunction "C_1") (pintype "passive"))
      (node (ref "S42") (pin "1") (pinfunction "C_1") (pintype "passive"))
      (node (ref "S43") (pin "1") (pinfunction "C_1") (pintype "passive"))
      (node (ref "S44") (pin "1") (pinfunction "C_1") (pintype "passive"))
      (node (ref "S45") (pin "1") (pinfunction "C_1") (pintype "passive"))
      (node (ref "S46") (pin "1") (pinfunction "C_1") (pintype "passive"))
      (node (ref "S47") (pin "1") (pinfunction "C_1") (pintype "passive"))
      (node (ref "S48") (pin "1") (pinfunction "C_1") (pintype "passive"))
    )
    (net (code "4") (name "/Sens_Col_3") (class "Default")
      (node (ref "J1") (pin "6") (pinfunction "6_6") (pintype "passive"))
      (node (ref "S49") (pin "1") (pinfunction "C_1") (pintype "passive"))
      (node (ref "S50") (pin "1") (pinfunction "C_1") (pintype "passive"))
      (node (ref "S51") (pin "1") (pinfunction "C_1") (pintype "passive"))
      (node (ref "S52") (pin "1") (pinfunction "C_1") (pintype "passive"))
      (node (ref "S53") (pin "1") (pinfunction "C_1") (pintype "passive"))
      (node (ref "S54") (pin "1") (pinfunction "C_1") (pintype "passive"))
      (node (ref "S55") (pin "1") (pinfunction "C_1") (pintype "passive"))
      (node (ref "S56") (pin "1") (pinfunction "C_1") (pintype "passive"))
      (node (ref "S57") (pin "1") (pinfunction "C_1") (pintype "passive"))
      (node (ref "S58") (pin "1") (pinfunction "C_1") (pintype "passive"))
      (node (ref "S59") (pin "1") (pinfunction "C_1") (pintype "passive"))
      (node (ref "S60") (pin "1") (pinfunction "C_1") (pintype "passive"))
      (node (ref "S61") (pin "1") (pinfunction "C_1") (pintype "passive"))
      (node (ref "S62") (pin "1") (pinfunction "C_1") (pintype "passive"))
      (node (ref "S63") (pin "1") (pinfunction "C_1") (pintype "passive"))
      (node (ref "S64") (pin "1") (pinfunction "C_1") (pintype "passive"))
    )
    (net (code "5") (name "/Sens_Col_4") (class "Default")
      (node (ref "J1") (pin "7") (pinfunction "7_7") (pintype "passive"))
      (node (ref "S65") (pin "1") (pinfunction "C_1") (pintype "passive"))
      (node (ref "S66") (pin "1") (pinfunction "C_1") (pintype "passive"))
      (node (ref "S67") (pin "1") (pinfunction "C_1") (pintype "passive"))
      (node (ref "S68") (pin "1") (pinfunction "C_1") (pintype "passive"))
      (node (ref "S69") (pin "1") (pinfunction "C_1") (pintype "passive"))
      (node (ref "S70") (pin "1") (pinfunction "C_1") (pintype "passive"))
      (node (ref "S71") (pin "1") (pinfunction "C_1") (pintype "passive"))
      (node (ref "S72") (pin "1") (pinfunction "C_1") (pintype "passive"))
      (node (ref "S73") (pin "1") (pinfunction "C_1") (pintype "passive"))
      (node (ref "S74") (pin "1") (pinfunction "C_1") (pintype "passive"))
      (node (ref "S75") (pin "1") (pinfunction "C_1") (pintype "passive"))
      (node (ref "S76") (pin "1") (pinfunction "C_1") (pintype "passive"))
      (node (ref "S77") (pin "1") (pinfunction "C_1") (pintype "passive"))
      (node (ref "S78") (pin "1") (pinfunction "C_1") (pintype "passive"))
      (node (ref "S79") (pin "1") (pinfunction "C_1") (pintype "passive"))
      (node (ref "S80") (pin "1") (pinfunction "C_1") (pintype "passive"))
    )
    (net (code "6") (name "/Sens_Col_5") (class "Default")
      (node (ref "J1") (pin "8") (pinfunction "8_8") (pintype "passive"))
      (node (ref "S81") (pin "1") (pinfunction "C_1") (pintype "passive"))
      (node (ref "S82") (pin "1") (pinfunction "C_1") (pintype "passive"))
      (node (ref "S83") (pin "1") (pinfunction "C_1") (pintype "passive"))
      (node (ref "S84") (pin "1") (pinfunction "C_1") (pintype "passive"))
      (node (ref "S85") (pin "1") (pinfunction "C_1") (pintype "passive"))
      (node (ref "S86") (pin "1") (pinfunction "C_1") (pintype "passive"))
      (node (ref "S87") (pin "1") (pinfunction "C_1") (pintype "passive"))
      (node (ref "S88") (pin "1") (pinfunction "C_1") (pintype "passive"))
      (node (ref "S89") (pin "1") (pinfunction "C_1") (pintype "passive"))
      (node (ref "S90") (pin "1") (pinfunction "C_1") (pintype "passive"))
      (node (ref "S91") (pin "1") (pinfunction "C_1") (pintype "passive"))
      (node (ref "S92") (pin "1") (pinfunction "C_1") (pintype "passive"))
      (node (ref "S93") (pin "1") (pinfunction "C_1") (pintype "passive"))
      (node (ref "S94") (pin "1") (pinfunction "C_1") (pintype "passive"))
      (node (ref "S95") (pin "1") (pinfunction "C_1") (pintype "passive"))
      (node (ref "S96") (pin "1") (pinfunction "C_1") (pintype "passive"))
    )
    (net (code "7") (name "/Sens_Col_6") (class "Default")
      (node (ref "J1") (pin "9") (pinfunction "9_9") (pintype "passive"))
      (node (ref "S100") (pin "1") (pinfunction "C_1") (pintype "passive"))
      (node (ref "S101") (pin "1") (pinfunction "C_1") (pintype "passive"))
      (node (ref "S102") (pin "1") (pinfunction "C_1") (pintype "passive"))
      (node (ref "S103") (pin "1") (pinfunction "C_1") (pintype "passive"))
      (node (ref "S104") (pin "1") (pinfunction "C_1") (pintype "passive"))
      (node (ref "S105") (pin "1") (pinfunction "C_1") (pintype "passive"))
      (node (ref "S106") (pin "1") (pinfunction "C_1") (pintype "passive"))
      (node (ref "S107") (pin "1") (pinfunction "C_1") (pintype "passive"))
      (node (ref "S108") (pin "1") (pinfunction "C_1") (pintype "passive"))
      (node (ref "S109") (pin "1") (pinfunction "C_1") (pintype "passive"))
      (node (ref "S110") (pin "1") (pinfunction "C_1") (pintype "passive"))
      (node (ref "S111") (pin "1") (pinfunction "C_1") (pintype "passive"))
      (node (ref "S112") (pin "1") (pinfunction "C_1") (pintype "passive"))
      (node (ref "S97") (pin "1") (pinfunction "C_1") (pintype "passive"))
      (node (ref "S98") (pin "1") (pinfunction "C_1") (pintype "passive"))
      (node (ref "S99") (pin "1") (pinfunction "C_1") (pintype "passive"))
    )
    (net (code "8") (name "/Sens_Col_7") (class "Default")
      (node (ref "J1") (pin "10") (pinfunction "10_10") (pintype "passive"))
      (node (ref "S113") (pin "1") (pinfunction "C_1") (pintype "passive"))
      (node (ref "S114") (pin "1") (pinfunction "C_1") (pintype "passive"))
      (node (ref "S115") (pin "1") (pinfunction "C_1") (pintype "passive"))
      (node (ref "S116") (pin "1") (pinfunction "C_1") (pintype "passive"))
      (node (ref "S117") (pin "1") (pinfunction "C_1") (pintype "passive"))
      (node (ref "S118") (pin "1") (pinfunction "C_1") (pintype "passive"))
      (node (ref "S119") (pin "1") (pinfunction "C_1") (pintype "passive"))
      (node (ref "S120") (pin "1") (pinfunction "C_1") (pintype "passive"))
      (node (ref "S121") (pin "1") (pinfunction "C_1") (pintype "passive"))
      (node (ref "S122") (pin "1") (pinfunction "C_1") (pintype "passive"))
      (node (ref "S123") (pin "1") (pinfunction "C_1") (pintype "passive"))
      (node (ref "S124") (pin "1") (pinfunction "C_1") (pintype "passive"))
      (node (ref "S125") (pin "1") (pinfunction "C_1") (pintype "passive"))
      (node (ref "S126") (pin "1") (pinfunction "C_1") (pintype "passive"))
      (node (ref "S127") (pin "1") (pinfunction "C_1") (pintype "passive"))
      (node (ref "S128") (pin "1") (pinfunction "C_1") (pintype "passive"))
    )
    (net (code "9") (name "/Sens_Col_8") (class "Default")
      (node (ref "J1") (pin "11") (pinfunction "11_11") (pintype "passive"))
      (node (ref "S129") (pin "1") (pinfunction "C_1") (pintype "passive"))
      (node (ref "S130") (pin "1") (pinfunction "C_1") (pintype "passive"))
      (node (ref "S131") (pin "1") (pinfunction "C_1") (pintype "passive"))
      (node (ref "S132") (pin "1") (pinfunction "C_1") (pintype "passive"))
      (node (ref "S133") (pin "1") (pinfunction "C_1") (pintype "passive"))
      (node (ref "S134") (pin "1") (pinfunction "C_1") (pintype "passive"))
      (node (ref "S135") (pin "1") (pinfunction "C_1") (pintype "passive"))
      (node (ref "S136") (pin "1") (pinfunction "C_1") (pintype "passive"))
      (node (ref "S137") (pin "1") (pinfunction "C_1") (pintype "passive"))
      (node (ref "S138") (pin "1") (pinfunction "C_1") (pintype "passive"))
      (node (ref "S139") (pin "1") (pinfunction "C_1") (pintype "passive"))
      (node (ref "S140") (pin "1") (pinfunction "C_1") (pintype "passive"))
      (node (ref "S141") (pin "1") (pinfunction "C_1") (pintype "passive"))
      (node (ref "S142") (pin "1") (pinfunction "C_1") (pintype "passive"))
      (node (ref "S143") (pin "1") (pinfunction "C_1") (pintype "passive"))
      (node (ref "S144") (pin "1") (pinfunction "C_1") (pintype "passive"))
    )
    (net (code "10") (name "/Sens_Col_9") (class "Default")
      (node (ref "J1") (pin "12") (pinfunction "12_12") (pintype "passive"))
      (node (ref "S145") (pin "1") (pinfunction "C_1") (pintype "passive"))
      (node (ref "S146") (pin "1") (pinfunction "C_1") (pintype "passive"))
      (node (ref "S147") (pin "1") (pinfunction "C_1") (pintype "passive"))
      (node (ref "S148") (pin "1") (pinfunction "C_1") (pintype "passive"))
      (node (ref "S149") (pin "1") (pinfunction "C_1") (pintype "passive"))
      (node (ref "S150") (pin "1") (pinfunction "C_1") (pintype "passive"))
      (node (ref "S151") (pin "1") (pinfunction "C_1") (pintype "passive"))
      (node (ref "S152") (pin "1") (pinfunction "C_1") (pintype "passive"))
      (node (ref "S153") (pin "1") (pinfunction "C_1") (pintype "passive"))
      (node (ref "S154") (pin "1") (pinfunction "C_1") (pintype "passive"))
      (node (ref "S155") (pin "1") (pinfunction "C_1") (pintype "passive"))
      (node (ref "S156") (pin "1") (pinfunction "C_1") (pintype "passive"))
      (node (ref "S157") (pin "1") (pinfunction "C_1") (pintype "passive"))
      (node (ref "S158") (pin "1") (pinfunction "C_1") (pintype "passive"))
      (node (ref "S159") (pin "1") (pinfunction "C_1") (pintype "passive"))
      (node (ref "S160") (pin "1") (pinfunction "C_1") (pintype "passive"))
    )
    (net (code "11") (name "/Sens_Col_10") (class "Default")
      (node (ref "J1") (pin "13") (pinfunction "13_13") (pintype "passive"))
      (node (ref "S161") (pin "1") (pinfunction "C_1") (pintype "passive"))
      (node (ref "S162") (pin "1") (pinfunction "C_1") (pintype "passive"))
      (node (ref "S163") (pin "1") (pinfunction "C_1") (pintype "passive"))
      (node (ref "S164") (pin "1") (pinfunction "C_1") (pintype "passive"))
      (node (ref "S165") (pin "1") (pinfunction "C_1") (pintype "passive"))
      (node (ref "S166") (pin "1") (pinfunction "C_1") (pintype "passive"))
      (node (ref "S167") (pin "1") (pinfunction "C_1") (pintype "passive"))
      (node (ref "S168") (pin "1") (pinfunction "C_1") (pintype "passive"))
      (node (ref "S169") (pin "1") (pinfunction "C_1") (pintype "passive"))
      (node (ref "S170") (pin "1") (pinfunction "C_1") (pintype "passive"))
      (node (ref "S171") (pin "1") (pinfunction "C_1") (pintype "passive"))
      (node (ref "S172") (pin "1") (pinfunction "C_1") (pintype "passive"))
      (node (ref "S173") (pin "1") (pinfunction "C_1") (pintype "passive"))
      (node (ref "S174") (pin "1") (pinfunction "C_1") (pintype "passive"))
      (node (ref "S175") (pin "1") (pinfunction "C_1") (pintype "passive"))
      (node (ref "S176") (pin "1") (pinfunction "C_1") (pintype "passive"))
    )
    (net (code "12") (name "/Sens_Col_11") (class "Default")
      (node (ref "J1") (pin "14") (pinfunction "14_14") (pintype "passive"))
      (node (ref "S177") (pin "1") (pinfunction "C_1") (pintype "passive"))
      (node (ref "S178") (pin "1") (pinfunction "C_1") (pintype "passive"))
      (node (ref "S179") (pin "1") (pinfunction "C_1") (pintype "passive"))
      (node (ref "S180") (pin "1") (pinfunction "C_1") (pintype "passive"))
      (node (ref "S181") (pin "1") (pinfunction "C_1") (pintype "passive"))
      (node (ref "S182") (pin "1") (pinfunction "C_1") (pintype "passive"))
      (node (ref "S183") (pin "1") (pinfunction "C_1") (pintype "passive"))
      (node (ref "S184") (pin "1") (pinfunction "C_1") (pintype "passive"))
      (node (ref "S185") (pin "1") (pinfunction "C_1") (pintype "passive"))
      (node (ref "S186") (pin "1") (pinfunction "C_1") (pintype "passive"))
      (node (ref "S187") (pin "1") (pinfunction "C_1") (pintype "passive"))
      (node (ref "S188") (pin "1") (pinfunction "C_1") (pintype "passive"))
      (node (ref "S189") (pin "1") (pinfunction "C_1") (pintype "passive"))
      (node (ref "S190") (pin "1") (pinfunction "C_1") (pintype "passive"))
      (node (ref "S191") (pin "1") (pinfunction "C_1") (pintype "passive"))
      (node (ref "S192") (pin "1") (pinfunction "C_1") (pintype "passive"))
    )
    (net (code "13") (name "/Sens_Col_12") (class "Default")
      (node (ref "J1") (pin "15") (pinfunction "15_15") (pintype "passive"))
      (node (ref "S193") (pin "1") (pinfunction "C_1") (pintype "passive"))
      (node (ref "S194") (pin "1") (pinfunction "C_1") (pintype "passive"))
      (node (ref "S195") (pin "1") (pinfunction "C_1") (pintype "passive"))
      (node (ref "S196") (pin "1") (pinfunction "C_1") (pintype "passive"))
      (node (ref "S197") (pin "1") (pinfunction "C_1") (pintype "passive"))
      (node (ref "S198") (pin "1") (pinfunction "C_1") (pintype "passive"))
      (node (ref "S199") (pin "1") (pinfunction "C_1") (pintype "passive"))
      (node (ref "S200") (pin "1") (pinfunction "C_1") (pintype "passive"))
      (node (ref "S201") (pin "1") (pinfunction "C_1") (pintype "passive"))
      (node (ref "S202") (pin "1") (pinfunction "C_1") (pintype "passive"))
      (node (ref "S203") (pin "1") (pinfunction "C_1") (pintype "passive"))
      (node (ref "S204") (pin "1") (pinfunction "C_1") (pintype "passive"))
      (node (ref "S205") (pin "1") (pinfunction "C_1") (pintype "passive"))
      (node (ref "S206") (pin "1") (pinfunction "C_1") (pintype "passive"))
      (node (ref "S207") (pin "1") (pinfunction "C_1") (pintype "passive"))
      (node (ref "S208") (pin "1") (pinfunction "C_1") (pintype "passive"))
    )
    (net (code "14") (name "/Sens_Col_13") (class "Default")
      (node (ref "J1") (pin "16") (pinfunction "16_16") (pintype "passive"))
      (node (ref "S209") (pin "1") (pinfunction "C_1") (pintype "passive"))
      (node (ref "S210") (pin "1") (pinfunction "C_1") (pintype "passive"))
      (node (ref "S211") (pin "1") (pinfunction "C_1") (pintype "passive"))
      (node (ref "S212") (pin "1") (pinfunction "C_1") (pintype "passive"))
      (node (ref "S213") (pin "1") (pinfunction "C_1") (pintype "passive"))
      (node (ref "S214") (pin "1") (pinfunction "C_1") (pintype "passive"))
      (node (ref "S215") (pin "1") (pinfunction "C_1") (pintype "passive"))
      (node (ref "S216") (pin "1") (pinfunction "C_1") (pintype "passive"))
      (node (ref "S217") (pin "1") (pinfunction "C_1") (pintype "passive"))
      (node (ref "S218") (pin "1") (pinfunction "C_1") (pintype "passive"))
      (node (ref "S219") (pin "1") (pinfunction "C_1") (pintype "passive"))
      (node (ref "S220") (pin "1") (pinfunction "C_1") (pintype "passive"))
      (node (ref "S221") (pin "1") (pinfunction "C_1") (pintype "passive"))
      (node (ref "S222") (pin "1") (pinfunction "C_1") (pintype "passive"))
      (node (ref "S223") (pin "1") (pinfunction "C_1") (pintype "passive"))
      (node (ref "S224") (pin "1") (pinfunction "C_1") (pintype "passive"))
    )
    (net (code "15") (name "/Sens_Col_14") (class "Default")
      (node (ref "J1") (pin "17") (pinfunction "17_17") (pintype "passive"))
      (node (ref "S225") (pin "1") (pinfunction "C_1") (pintype "passive"))
      (node (ref "S226") (pin "1") (pinfunction "C_1") (pintype "passive"))
      (node (ref "S227") (pin "1") (pinfunction "C_1") (pintype "passive"))
      (node (ref "S228") (pin "1") (pinfunction "C_1") (pintype "passive"))
      (node (ref "S229") (pin "1") (pinfunction "C_1") (pintype "passive"))
      (node (ref "S230") (pin "1") (pinfunction "C_1") (pintype "passive"))
      (node (ref "S231") (pin "1") (pinfunction "C_1") (pintype "passive"))
      (node (ref "S232") (pin "1") (pinfunction "C_1") (pintype "passive"))
      (node (ref "S233") (pin "1") (pinfunction "C_1") (pintype "passive"))
      (node (ref "S234") (pin "1") (pinfunction "C_1") (pintype "passive"))
      (node (ref "S235") (pin "1") (pinfunction "C_1") (pintype "passive"))
      (node (ref "S236") (pin "1") (pinfunction "C_1") (pintype "passive"))
      (node (ref "S237") (pin "1") (pinfunction "C_1") (pintype "passive"))
      (node (ref "S238") (pin "1") (pinfunction "C_1") (pintype "passive"))
      (node (ref "S239") (pin "1") (pinfunction "C_1") (pintype "passive"))
      (node (ref "S240") (pin "1") (pinfunction "C_1") (pintype "passive"))
    )
    (net (code "16") (name "/Sens_Col_15") (class "Default")
      (node (ref "J1") (pin "18") (pinfunction "18_18") (pintype "passive"))
      (node (ref "S241") (pin "1") (pinfunction "C_1") (pintype "passive"))
      (node (ref "S242") (pin "1") (pinfunction "C_1") (pintype "passive"))
      (node (ref "S243") (pin "1") (pinfunction "C_1") (pintype "passive"))
      (node (ref "S244") (pin "1") (pinfunction "C_1") (pintype "passive"))
      (node (ref "S245") (pin "1") (pinfunction "C_1") (pintype "passive"))
      (node (ref "S246") (pin "1") (pinfunction "C_1") (pintype "passive"))
      (node (ref "S247") (pin "1") (pinfunction "C_1") (pintype "passive"))
      (node (ref "S248") (pin "1") (pinfunction "C_1") (pintype "passive"))
      (node (ref "S249") (pin "1") (pinfunction "C_1") (pintype "passive"))
      (node (ref "S250") (pin "1") (pinfunction "C_1") (pintype "passive"))
      (node (ref "S251") (pin "1") (pinfunction "C_1") (pintype "passive"))
      (node (ref "S252") (pin "1") (pinfunction "C_1") (pintype "passive"))
      (node (ref "S253") (pin "1") (pinfunction "C_1") (pintype "passive"))
      (node (ref "S254") (pin "1") (pinfunction "C_1") (pintype "passive"))
      (node (ref "S255") (pin "1") (pinfunction "C_1") (pintype "passive"))
      (node (ref "S256") (pin "1") (pinfunction "C_1") (pintype "passive"))
    )
    (net (code "18") (name "/Sens_Row_0") (class "Default")
      (node (ref "J1") (pin "19") (pinfunction "19_19") (pintype "passive"))
      (node (ref "S112") (pin "2") (pinfunction "R_2") (pintype "passive"))
      (node (ref "S128") (pin "2") (pinfunction "R_2") (pintype "passive"))
      (node (ref "S144") (pin "2") (pinfunction "R_2") (pintype "passive"))
      (node (ref "S16") (pin "2") (pinfunction "R_2") (pintype "passive"))
      (node (ref "S160") (pin "2") (pinfunction "R_2") (pintype "passive"))
      (node (ref "S176") (pin "2") (pinfunction "R_2") (pintype "passive"))
      (node (ref "S192") (pin "2") (pinfunction "R_2") (pintype "passive"))
      (node (ref "S208") (pin "2") (pinfunction "R_2") (pintype "passive"))
      (node (ref "S224") (pin "2") (pinfunction "R_2") (pintype "passive"))
      (node (ref "S240") (pin "2") (pinfunction "R_2") (pintype "passive"))
      (node (ref "S256") (pin "2") (pinfunction "R_2") (pintype "passive"))
      (node (ref "S32") (pin "2") (pinfunction "R_2") (pintype "passive"))
      (node (ref "S48") (pin "2") (pinfunction "R_2") (pintype "passive"))
      (node (ref "S64") (pin "2") (pinfunction "R_2") (pintype "passive"))
      (node (ref "S80") (pin "2") (pinfunction "R_2") (pintype "passive"))
      (node (ref "S96") (pin "2") (pinfunction "R_2") (pintype "passive"))
    )
    (net (code "19") (name "/Sens_Row_1") (class "Default")
      (node (ref "J1") (pin "20") (pinfunction "20_20") (pintype "passive"))
      (node (ref "S111") (pin "2") (pinfunction "R_2") (pintype "passive"))
      (node (ref "S127") (pin "2") (pinfunction "R_2") (pintype "passive"))
      (node (ref "S143") (pin "2") (pinfunction "R_2") (pintype "passive"))
      (node (ref "S15") (pin "2") (pinfunction "R_2") (pintype "passive"))
      (node (ref "S159") (pin "2") (pinfunction "R_2") (pintype "passive"))
      (node (ref "S175") (pin "2") (pinfunction "R_2") (pintype "passive"))
      (node (ref "S191") (pin "2") (pinfunction "R_2") (pintype "passive"))
      (node (ref "S207") (pin "2") (pinfunction "R_2") (pintype "passive"))
      (node (ref "S223") (pin "2") (pinfunction "R_2") (pintype "passive"))
      (node (ref "S239") (pin "2") (pinfunction "R_2") (pintype "passive"))
      (node (ref "S255") (pin "2") (pinfunction "R_2") (pintype "passive"))
      (node (ref "S31") (pin "2") (pinfunction "R_2") (pintype "passive"))
      (node (ref "S47") (pin "2") (pinfunction "R_2") (pintype "passive"))
      (node (ref "S63") (pin "2") (pinfunction "R_2") (pintype "passive"))
      (node (ref "S79") (pin "2") (pinfunction "R_2") (pintype "passive"))
      (node (ref "S95") (pin "2") (pinfunction "R_2") (pintype "passive"))
    )
    (net (code "20") (name "/Sens_Row_2") (class "Default")
      (node (ref "J1") (pin "21") (pinfunction "21_21") (pintype "passive"))
      (node (ref "S110") (pin "2") (pinfunction "R_2") (pintype "passive"))
      (node (ref "S126") (pin "2") (pinfunction "R_2") (pintype "passive"))
      (node (ref "S14") (pin "2") (pinfunction "R_2") (pintype "passive"))
      (node (ref "S142") (pin "2") (pinfunction "R_2") (pintype "passive"))
      (node (ref "S158") (pin "2") (pinfunction "R_2") (pintype "passive"))
      (node (ref "S174") (pin "2") (pinfunction "R_2") (pintype "passive"))
      (node (ref "S190") (pin "2") (pinfunction "R_2") (pintype "passive"))
      (node (ref "S206") (pin "2") (pinfunction "R_2") (pintype "passive"))
      (node (ref "S222") (pin "2") (pinfunction "R_2") (pintype "passive"))
      (node (ref "S238") (pin "2") (pinfunction "R_2") (pintype "passive"))
      (node (ref "S254") (pin "2") (pinfunction "R_2") (pintype "passive"))
      (node (ref "S30") (pin "2") (pinfunction "R_2") (pintype "passive"))
      (node (ref "S46") (pin "2") (pinfunction "R_2") (pintype "passive"))
      (node (ref "S62") (pin "2") (pinfunction "R_2") (pintype "passive"))
      (node (ref "S78") (pin "2") (pinfunction "R_2") (pintype "passive"))
      (node (ref "S94") (pin "2") (pinfunction "R_2") (pintype "passive"))
    )
    (net (code "21") (name "/Sens_Row_3") (class "Default")
      (node (ref "J1") (pin "22") (pinfunction "22_22") (pintype "passive"))
      (node (ref "S109") (pin "2") (pinfunction "R_2") (pintype "passive"))
      (node (ref "S125") (pin "2") (pinfunction "R_2") (pintype "passive"))
      (node (ref "S13") (pin "2") (pinfunction "R_2") (pintype "passive"))
      (node (ref "S141") (pin "2") (pinfunction "R_2") (pintype "passive"))
      (node (ref "S157") (pin "2") (pinfunction "R_2") (pintype "passive"))
      (node (ref "S173") (pin "2") (pinfunction "R_2") (pintype "passive"))
      (node (ref "S189") (pin "2") (pinfunction "R_2") (pintype "passive"))
      (node (ref "S205") (pin "2") (pinfunction "R_2") (pintype "passive"))
      (node (ref "S221") (pin "2") (pinfunction "R_2") (pintype "passive"))
      (node (ref "S237") (pin "2") (pinfunction "R_2") (pintype "passive"))
      (node (ref "S253") (pin "2") (pinfunction "R_2") (pintype "passive"))
      (node (ref "S29") (pin "2") (pinfunction "R_2") (pintype "passive"))
      (node (ref "S45") (pin "2") (pinfunction "R_2") (pintype "passive"))
      (node (ref "S61") (pin "2") (pinfunction "R_2") (pintype "passive"))
      (node (ref "S77") (pin "2") (pinfunction "R_2") (pintype "passive"))
      (node (ref "S93") (pin "2") (pinfunction "R_2") (pintype "passive"))
    )
    (net (code "22") (name "/Sens_Row_4") (class "Default")
      (node (ref "J1") (pin "23") (pinfunction "23_23") (pintype "passive"))
      (node (ref "S108") (pin "2") (pinfunction "R_2") (pintype "passive"))
      (node (ref "S12") (pin "2") (pinfunction "R_2") (pintype "passive"))
      (node (ref "S124") (pin "2") (pinfunction "R_2") (pintype "passive"))
      (node (ref "S140") (pin "2") (pinfunction "R_2") (pintype "passive"))
      (node (ref "S156") (pin "2") (pinfunction "R_2") (pintype "passive"))
      (node (ref "S172") (pin "2") (pinfunction "R_2") (pintype "passive"))
      (node (ref "S188") (pin "2") (pinfunction "R_2") (pintype "passive"))
      (node (ref "S204") (pin "2") (pinfunction "R_2") (pintype "passive"))
      (node (ref "S220") (pin "2") (pinfunction "R_2") (pintype "passive"))
      (node (ref "S236") (pin "2") (pinfunction "R_2") (pintype "passive"))
      (node (ref "S252") (pin "2") (pinfunction "R_2") (pintype "passive"))
      (node (ref "S28") (pin "2") (pinfunction "R_2") (pintype "passive"))
      (node (ref "S44") (pin "2") (pinfunction "R_2") (pintype "passive"))
      (node (ref "S60") (pin "2") (pinfunction "R_2") (pintype "passive"))
      (node (ref "S76") (pin "2") (pinfunction "R_2") (pintype "passive"))
      (node (ref "S92") (pin "2") (pinfunction "R_2") (pintype "passive"))
    )
    (net (code "23") (name "/Sens_Row_5") (class "Default")
      (node (ref "J1") (pin "24") (pinfunction "24_24") (pintype "passive"))
      (node (ref "S107") (pin "2") (pinfunction "R_2") (pintype "passive"))
      (node (ref "S11") (pin "2") (pinfunction "R_2") (pintype "passive"))
      (node (ref "S123") (pin "2") (pinfunction "R_2") (pintype "passive"))
      (node (ref "S139") (pin "2") (pinfunction "R_2") (pintype "passive"))
      (node (ref "S155") (pin "2") (pinfunction "R_2") (pintype "passive"))
      (node (ref "S171") (pin "2") (pinfunction "R_2") (pintype "passive"))
      (node (ref "S187") (pin "2") (pinfunction "R_2") (pintype "passive"))
      (node (ref "S203") (pin "2") (pinfunction "R_2") (pintype "passive"))
      (node (ref "S219") (pin "2") (pinfunction "R_2") (pintype "passive"))
      (node (ref "S235") (pin "2") (pinfunction "R_2") (pintype "passive"))
      (node (ref "S251") (pin "2") (pinfunction "R_2") (pintype "passive"))
      (node (ref "S27") (pin "2") (pinfunction "R_2") (pintype "passive"))
      (node (ref "S43") (pin "2") (pinfunction "R_2") (pintype "passive"))
      (node (ref "S59") (pin "2") (pinfunction "R_2") (pintype "passive"))
      (node (ref "S75") (pin "2") (pinfunction "R_2") (pintype "passive"))
      (node (ref "S91") (pin "2") (pinfunction "R_2") (pintype "passive"))
    )
    (net (code "24") (name "/Sens_Row_6") (class "Default")
      (node (ref "J1") (pin "25") (pinfunction "25_25") (pintype "passive"))
      (node (ref "S10") (pin "2") (pinfunction "R_2") (pintype "passive"))
      (node (ref "S106") (pin "2") (pinfunction "R_2") (pintype "passive"))
      (node (ref "S122") (pin "2") (pinfunction "R_2") (pintype "passive"))
      (node (ref "S138") (pin "2") (pinfunction "R_2") (pintype "passive"))
      (node (ref "S154") (pin "2") (pinfunction "R_2") (pintype "passive"))
      (node (ref "S170") (pin "2") (pinfunction "R_2") (pintype "passive"))
      (node (ref "S186") (pin "2") (pinfunction "R_2") (pintype "passive"))
      (node (ref "S202") (pin "2") (pinfunction "R_2") (pintype "passive"))
      (node (ref "S218") (pin "2") (pinfunction "R_2") (pintype "passive"))
      (node (ref "S234") (pin "2") (pinfunction "R_2") (pintype "passive"))
      (node (ref "S250") (pin "2") (pinfunction "R_2") (pintype "passive"))
      (node (ref "S26") (pin "2") (pinfunction "R_2") (pintype "passive"))
      (node (ref "S42") (pin "2") (pinfunction "R_2") (pintype "passive"))
      (node (ref "S58") (pin "2") (pinfunction "R_2") (pintype "passive"))
      (node (ref "S74") (pin "2") (pinfunction "R_2") (pintype "passive"))
      (node (ref "S90") (pin "2") (pinfunction "R_2") (pintype "passive"))
    )
    (net (code "25") (name "/Sens_Row_7") (class "Default")
      (node (ref "J1") (pin "26") (pinfunction "26_26") (pintype "passive"))
      (node (ref "S105") (pin "2") (pinfunction "R_2") (pintype "passive"))
      (node (ref "S121") (pin "2") (pinfunction "R_2") (pintype "passive"))
      (node (ref "S137") (pin "2") (pinfunction "R_2") (pintype "passive"))
      (node (ref "S153") (pin "2") (pinfunction "R_2") (pintype "passive"))
      (node (ref "S169") (pin "2") (pinfunction "R_2") (pintype "passive"))
      (node (ref "S185") (pin "2") (pinfunction "R_2") (pintype "passive"))
      (node (ref "S201") (pin "2") (pinfunction "R_2") (pintype "passive"))
      (node (ref "S217") (pin "2") (pinfunction "R_2") (pintype "passive"))
      (node (ref "S233") (pin "2") (pinfunction "R_2") (pintype "passive"))
      (node (ref "S249") (pin "2") (pinfunction "R_2") (pintype "passive"))
      (node (ref "S25") (pin "2") (pinfunction "R_2") (pintype "passive"))
      (node (ref "S41") (pin "2") (pinfunction "R_2") (pintype "passive"))
      (node (ref "S57") (pin "2") (pinfunction "R_2") (pintype "passive"))
      (node (ref "S73") (pin "2") (pinfunction "R_2") (pintype "passive"))
      (node (ref "S89") (pin "2") (pinfunction "R_2") (pintype "passive"))
      (node (ref "S9") (pin "2") (pinfunction "R_2") (pintype "passive"))
    )
    (net (code "26") (name "/Sens_Row_8") (class "Default")
      (node (ref "J1") (pin "27") (pinfunction "27_27") (pintype "passive"))
      (node (ref "S104") (pin "2") (pinfunction "R_2") (pintype "passive"))
      (node (ref "S120") (pin "2") (pinfunction "R_2") (pintype "passive"))
      (node (ref "S136") (pin "2") (pinfunction "R_2") (pintype "passive"))
      (node (ref "S152") (pin "2") (pinfunction "R_2") (pintype "passive"))
      (node (ref "S168") (pin "2") (pinfunction "R_2") (pintype "passive"))
      (node (ref "S184") (pin "2") (pinfunction "R_2") (pintype "passive"))
      (node (ref "S200") (pin "2") (pinfunction "R_2") (pintype "passive"))
      (node (ref "S216") (pin "2") (pinfunction "R_2") (pintype "passive"))
      (node (ref "S232") (pin "2") (pinfunction "R_2") (pintype "passive"))
      (node (ref "S24") (pin "2") (pinfunction "R_2") (pintype "passive"))
      (node (ref "S248") (pin "2") (pinfunction "R_2") (pintype "passive"))
      (node (ref "S40") (pin "2") (pinfunction "R_2") (pintype "passive"))
      (node (ref "S56") (pin "2") (pinfunction "R_2") (pintype "passive"))
      (node (ref "S72") (pin "2") (pinfunction "R_2") (pintype "passive"))
      (node (ref "S8") (pin "2") (pinfunction "R_2") (pintype "passive"))
      (node (ref "S88") (pin "2") (pinfunction "R_2") (pintype "passive"))
    )
    (net (code "27") (name "/Sens_Row_9") (class "Default")
      (node (ref "J1") (pin "28") (pinfunction "28_28") (pintype "passive"))
      (node (ref "S103") (pin "2") (pinfunction "R_2") (pintype "passive"))
      (node (ref "S119") (pin "2") (pinfunction "R_2") (pintype "passive"))
      (node (ref "S135") (pin "2") (pinfunction "R_2") (pintype "passive"))
      (node (ref "S151") (pin "2") (pinfunction "R_2") (pintype "passive"))
      (node (ref "S167") (pin "2") (pinfunction "R_2") (pintype "passive"))
      (node (ref "S183") (pin "2") (pinfunction "R_2") (pintype "passive"))
      (node (ref "S199") (pin "2") (pinfunction "R_2") (pintype "passive"))
      (node (ref "S215") (pin "2") (pinfunction "R_2") (pintype "passive"))
      (node (ref "S23") (pin "2") (pinfunction "R_2") (pintype "passive"))
      (node (ref "S231") (pin "2") (pinfunction "R_2") (pintype "passive"))
      (node (ref "S247") (pin "2") (pinfunction "R_2") (pintype "passive"))
      (node (ref "S39") (pin "2") (pinfunction "R_2") (pintype "passive"))
      (node (ref "S55") (pin "2") (pinfunction "R_2") (pintype "passive"))
      (node (ref "S7") (pin "2") (pinfunction "R_2") (pintype "passive"))
      (node (ref "S71") (pin "2") (pinfunction "R_2") (pintype "passive"))
      (node (ref "S87") (pin "2") (pinfunction "R_2") (pintype "passive"))
    )
    (net (code "28") (name "/Sens_Row_10") (class "Default")
      (node (ref "J1") (pin "29") (pinfunction "29_29") (pintype "passive"))
      (node (ref "S102") (pin "2") (pinfunction "R_2") (pintype "passive"))
      (node (ref "S118") (pin "2") (pinfunction "R_2") (pintype "passive"))
      (node (ref "S134") (pin "2") (pinfunction "R_2") (pintype "passive"))
      (node (ref "S150") (pin "2") (pinfunction "R_2") (pintype "passive"))
      (node (ref "S166") (pin "2") (pinfunction "R_2") (pintype "passive"))
      (node (ref "S182") (pin "2") (pinfunction "R_2") (pintype "passive"))
      (node (ref "S198") (pin "2") (pinfunction "R_2") (pintype "passive"))
      (node (ref "S214") (pin "2") (pinfunction "R_2") (pintype "passive"))
      (node (ref "S22") (pin "2") (pinfunction "R_2") (pintype "passive"))
      (node (ref "S230") (pin "2") (pinfunction "R_2") (pintype "passive"))
      (node (ref "S246") (pin "2") (pinfunction "R_2") (pintype "passive"))
      (node (ref "S38") (pin "2") (pinfunction "R_2") (pintype "passive"))
      (node (ref "S54") (pin "2") (pinfunction "R_2") (pintype "passive"))
      (node (ref "S6") (pin "2") (pinfunction "R_2") (pintype "passive"))
      (node (ref "S70") (pin "2") (pinfunction "R_2") (pintype "passive"))
      (node (ref "S86") (pin "2") (pinfunction "R_2") (pintype "passive"))
    )
    (net (code "29") (name "/Sens_Row_11") (class "Default")
      (node (ref "J1") (pin "30") (pinfunction "30_30") (pintype "passive"))
      (node (ref "S101") (pin "2") (pinfunction "R_2") (pintype "passive"))
      (node (ref "S117") (pin "2") (pinfunction "R_2") (pintype "passive"))
      (node (ref "S133") (pin "2") (pinfunction "R_2") (pintype "passive"))
      (node (ref "S149") (pin "2") (pinfunction "R_2") (pintype "passive"))
      (node (ref "S165") (pin "2") (pinfunction "R_2") (pintype "passive"))
      (node (ref "S181") (pin "2") (pinfunction "R_2") (pintype "passive"))
      (node (ref "S197") (pin "2") (pinfunction "R_2") (pintype "passive"))
      (node (ref "S21") (pin "2") (pinfunction "R_2") (pintype "passive"))
      (node (ref "S213") (pin "2") (pinfunction "R_2") (pintype "passive"))
      (node (ref "S229") (pin "2") (pinfunction "R_2") (pintype "passive"))
      (node (ref "S245") (pin "2") (pinfunction "R_2") (pintype "passive"))
      (node (ref "S37") (pin "2") (pinfunction "R_2") (pintype "passive"))
      (node (ref "S5") (pin "2") (pinfunction "R_2") (pintype "passive"))
      (node (ref "S53") (pin "2") (pinfunction "R_2") (pintype "passive"))
      (node (ref "S69") (pin "2") (pinfunction "R_2") (pintype "passive"))
      (node (ref "S85") (pin "2") (pinfunction "R_2") (pintype "passive"))
    )
    (net (code "30") (name "/Sens_Row_12") (class "Default")
      (node (ref "J1") (pin "31") (pinfunction "31_31") (pintype "passive"))
      (node (ref "S100") (pin "2") (pinfunction "R_2") (pintype "passive"))
      (node (ref "S116") (pin "2") (pinfunction "R_2") (pintype "passive"))
      (node (ref "S132") (pin "2") (pinfunction "R_2") (pintype "passive"))
      (node (ref "S148") (pin "2") (pinfunction "R_2") (pintype "passive"))
      (node (ref "S164") (pin "2") (pinfunction "R_2") (pintype "passive"))
      (node (ref "S180") (pin "2") (pinfunction "R_2") (pintype "passive"))
      (node (ref "S196") (pin "2") (pinfunction "R_2") (pintype "passive"))
      (node (ref "S20") (pin "2") (pinfunction "R_2") (pintype "passive"))
      (node (ref "S212") (pin "2") (pinfunction "R_2") (pintype "passive"))
      (node (ref "S228") (pin "2") (pinfunction "R_2") (pintype "passive"))
      (node (ref "S244") (pin "2") (pinfunction "R_2") (pintype "passive"))
      (node (ref "S36") (pin "2") (pinfunction "R_2") (pintype "passive"))
      (node (ref "S4") (pin "2") (pinfunction "R_2") (pintype "passive"))
      (node (ref "S52") (pin "2") (pinfunction "R_2") (pintype "passive"))
      (node (ref "S68") (pin "2") (pinfunction "R_2") (pintype "passive"))
      (node (ref "S84") (pin "2") (pinfunction "R_2") (pintype "passive"))
    )
    (net (code "31") (name "/Sens_Row_13") (class "Default")
      (node (ref "J1") (pin "32") (pinfunction "32_32") (pintype "passive"))
      (node (ref "S115") (pin "2") (pinfunction "R_2") (pintype "passive"))
      (node (ref "S131") (pin "2") (pinfunction "R_2") (pintype "passive"))
      (node (ref "S147") (pin "2") (pinfunction "R_2") (pintype "passive"))
      (node (ref "S163") (pin "2") (pinfunction "R_2") (pintype "passive"))
      (node (ref "S179") (pin "2") (pinfunction "R_2") (pintype "passive"))
      (node (ref "S19") (pin "2") (pinfunction "R_2") (pintype "passive"))
      (node (ref "S195") (pin "2") (pinfunction "R_2") (pintype "passive"))
      (node (ref "S211") (pin "2") (pinfunction "R_2") (pintype "passive"))
      (node (ref "S227") (pin "2") (pinfunction "R_2") (pintype "passive"))
      (node (ref "S243") (pin "2") (pinfunction "R_2") (pintype "passive"))
      (node (ref "S3") (pin "2") (pinfunction "R_2") (pintype "passive"))
      (node (ref "S35") (pin "2") (pinfunction "R_2") (pintype "passive"))
      (node (ref "S51") (pin "2") (pinfunction "R_2") (pintype "passive"))
      (node (ref "S67") (pin "2") (pinfunction "R_2") (pintype "passive"))
      (node (ref "S83") (pin "2") (pinfunction "R_2") (pintype "passive"))
      (node (ref "S99") (pin "2") (pinfunction "R_2") (pintype "passive"))
    )
    (net (code "32") (name "/Sens_Row_14") (class "Default")
      (node (ref "J1") (pin "33") (pinfunction "33_33") (pintype "passive"))
      (node (ref "S114") (pin "2") (pinfunction "R_2") (pintype "passive"))
      (node (ref "S130") (pin "2") (pinfunction "R_2") (pintype "passive"))
      (node (ref "S146") (pin "2") (pinfunction "R_2") (pintype "passive"))
      (node (ref "S162") (pin "2") (pinfunction "R_2") (pintype "passive"))
      (node (ref "S178") (pin "2") (pinfunction "R_2") (pintype "passive"))
      (node (ref "S18") (pin "2") (pinfunction "R_2") (pintype "passive"))
      (node (ref "S194") (pin "2") (pinfunction "R_2") (pintype "passive"))
      (node (ref "S2") (pin "2") (pinfunction "R_2") (pintype "passive"))
      (node (ref "S210") (pin "2") (pinfunction "R_2") (pintype "passive"))
      (node (ref "S226") (pin "2") (pinfunction "R_2") (pintype "passive"))
      (node (ref "S242") (pin "2") (pinfunction "R_2") (pintype "passive"))
      (node (ref "S34") (pin "2") (pinfunction "R_2") (pintype "passive"))
      (node (ref "S50") (pin "2") (pinfunction "R_2") (pintype "passive"))
      (node (ref "S66") (pin "2") (pinfunction "R_2") (pintype "passive"))
      (node (ref "S82") (pin "2") (pinfunction "R_2") (pintype "passive"))
      (node (ref "S98") (pin "2") (pinfunction "R_2") (pintype "passive"))
    )
    (net (code "33") (name "/Sens_Row_15") (class "Default")
      (node (ref "J1") (pin "34") (pinfunction "34_34") (pintype "passive"))
      (node (ref "S1") (pin "2") (pinfunction "R_2") (pintype "passive"))
      (node (ref "S113") (pin "2") (pinfunction "R_2") (pintype "passive"))
      (node (ref "S129") (pin "2") (pinfunction "R_2") (pintype "passive"))
      (node (ref "S145") (pin "2") (pinfunction "R_2") (pintype "passive"))
      (node (ref "S161") (pin "2") (pinfunction "R_2") (pintype "passive"))
      (node (ref "S17") (pin "2") (pinfunction "R_2") (pintype "passive"))
      (node (ref "S177") (pin "2") (pinfunction "R_2") (pintype "passive"))
      (node (ref "S193") (pin "2") (pinfunction "R_2") (pintype "passive"))
      (node (ref "S209") (pin "2") (pinfunction "R_2") (pintype "passive"))
      (node (ref "S225") (pin "2") (pinfunction "R_2") (pintype "passive"))
      (node (ref "S241") (pin "2") (pinfunction "R_2") (pintype "passive"))
      (node (ref "S33") (pin "2") (pinfunction "R_2") (pintype "passive"))
      (node (ref "S49") (pin "2") (pinfunction "R_2") (pintype "passive"))
      (node (ref "S65") (pin "2") (pinfunction "R_2") (pintype "passive"))
      (node (ref "S81") (pin "2") (pinfunction "R_2") (pintype "passive"))
      (node (ref "S97") (pin "2") (pinfunction "R_2") (pintype "passive"))
    )
    (net (code "34") (name "GND") (class "Default")
      (node (ref "J1") (pin "2") (pinfunction "2_2") (pintype "passive"))
    )
    (net (code "35") (name "VIN") (class "Default")
      (node (ref "J1") (pin "1") (pinfunction "1_1") (pintype "passive"))
    )
  )
)
